# DC-DC_Converter.net
KiCad netlist of a schematic drawn in Altium Designer
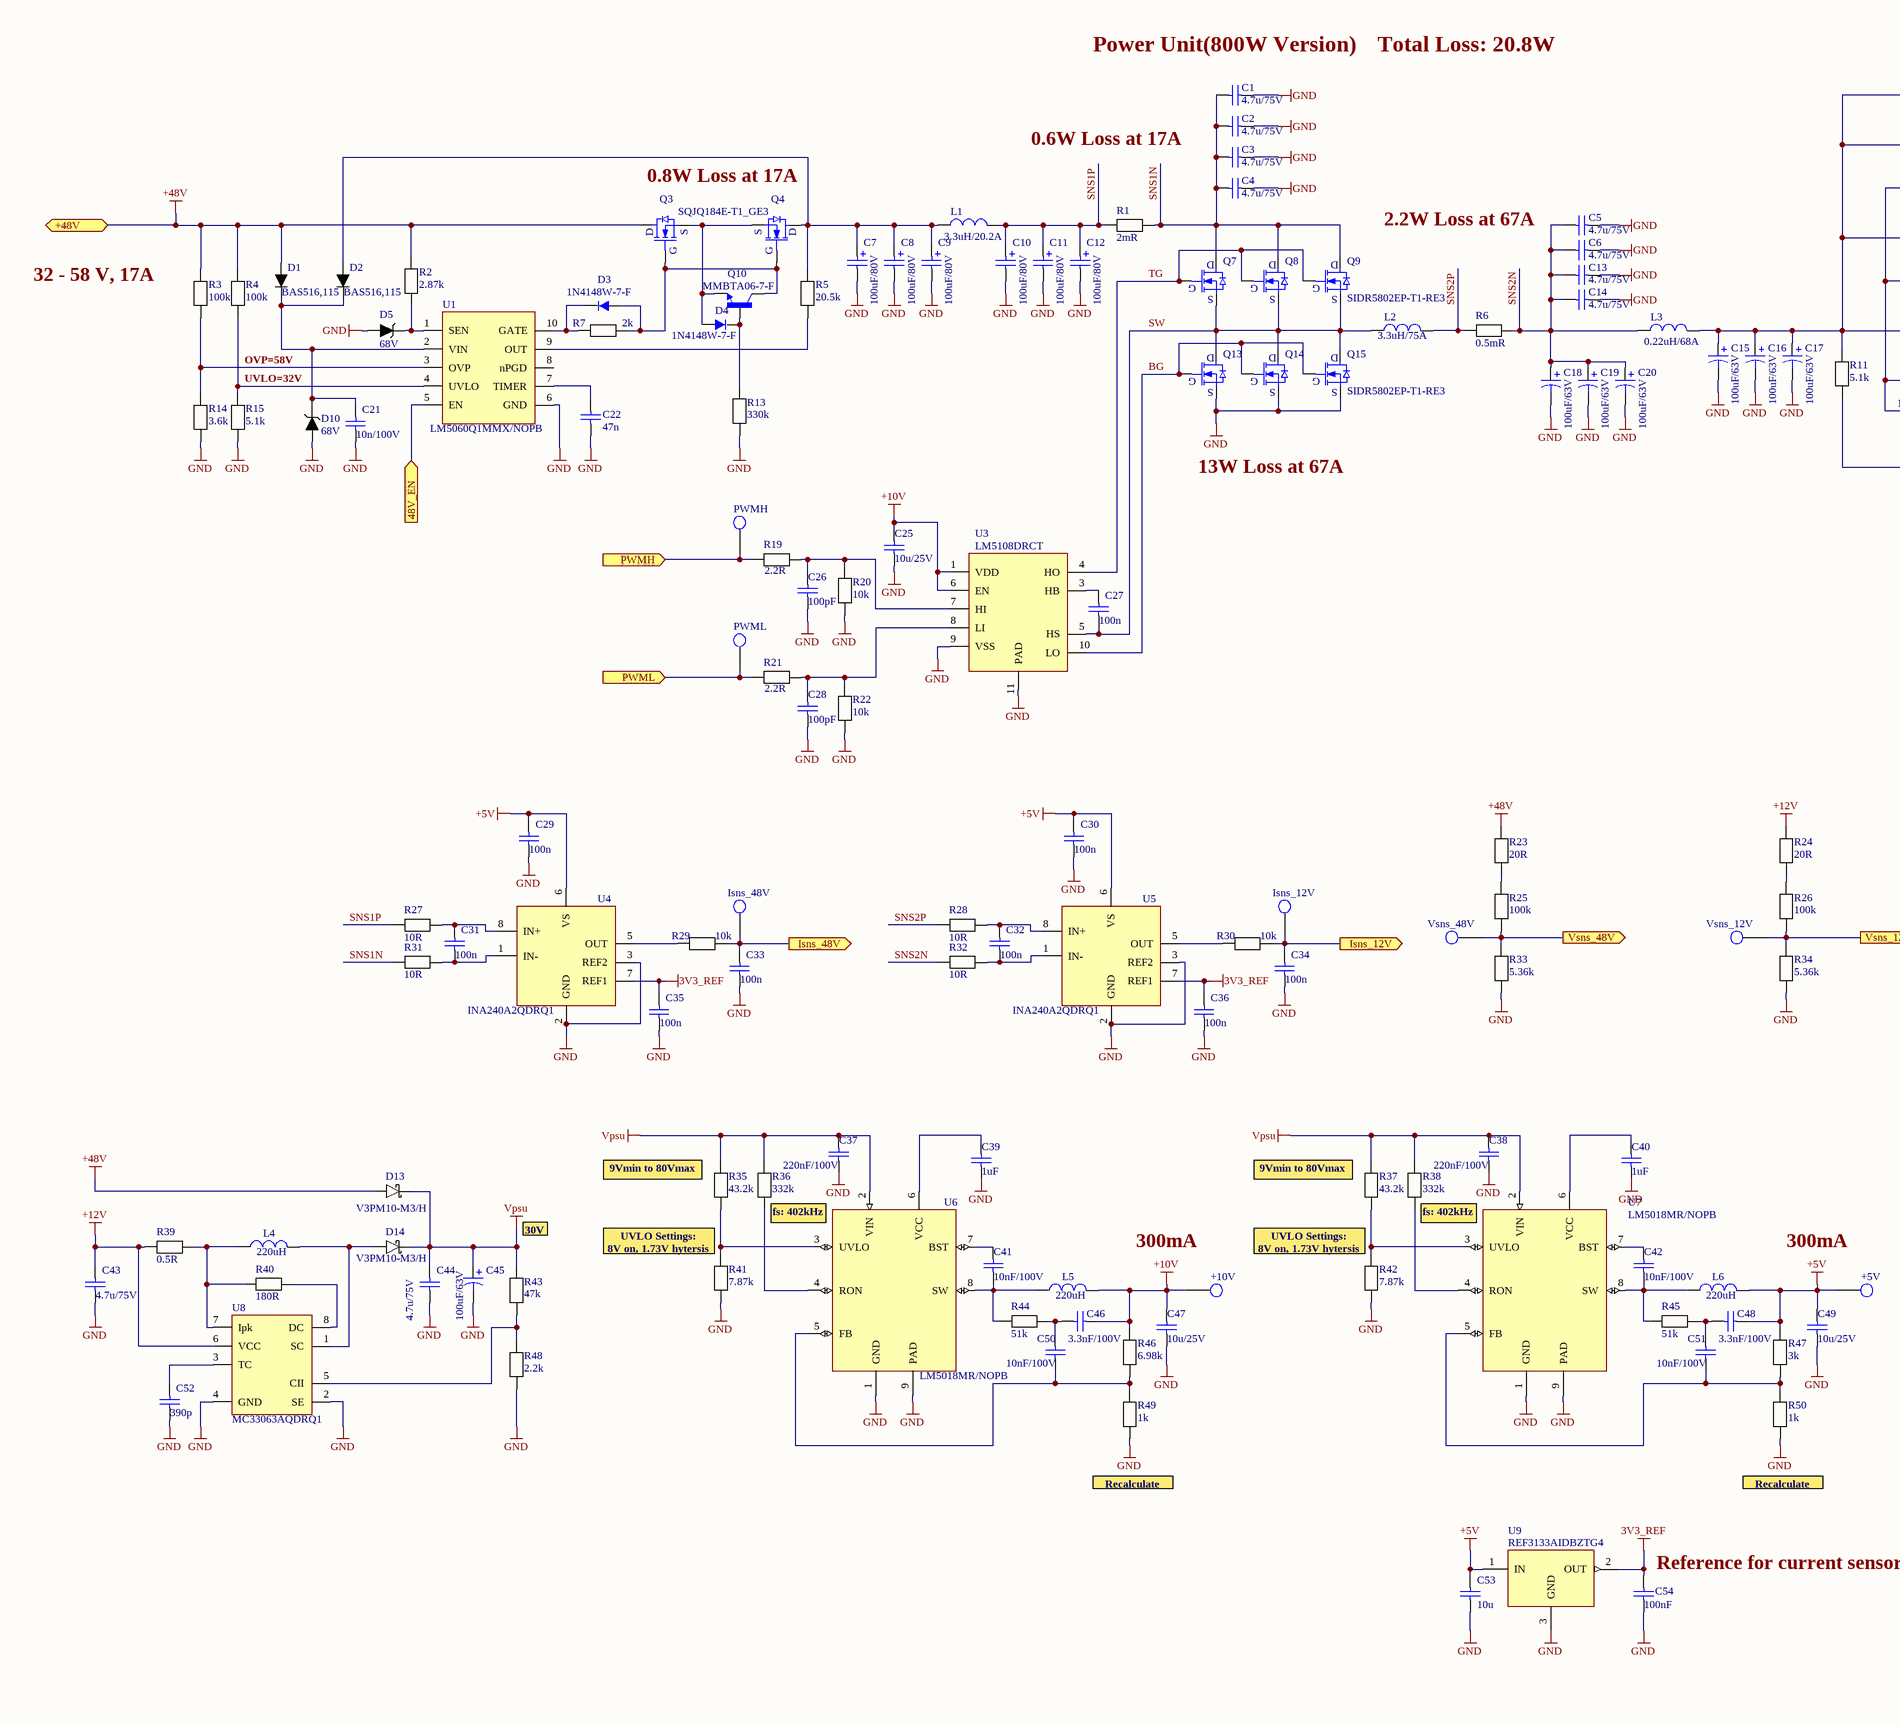
[diagram p0: DC-DC_Converter.SchDoc, left]
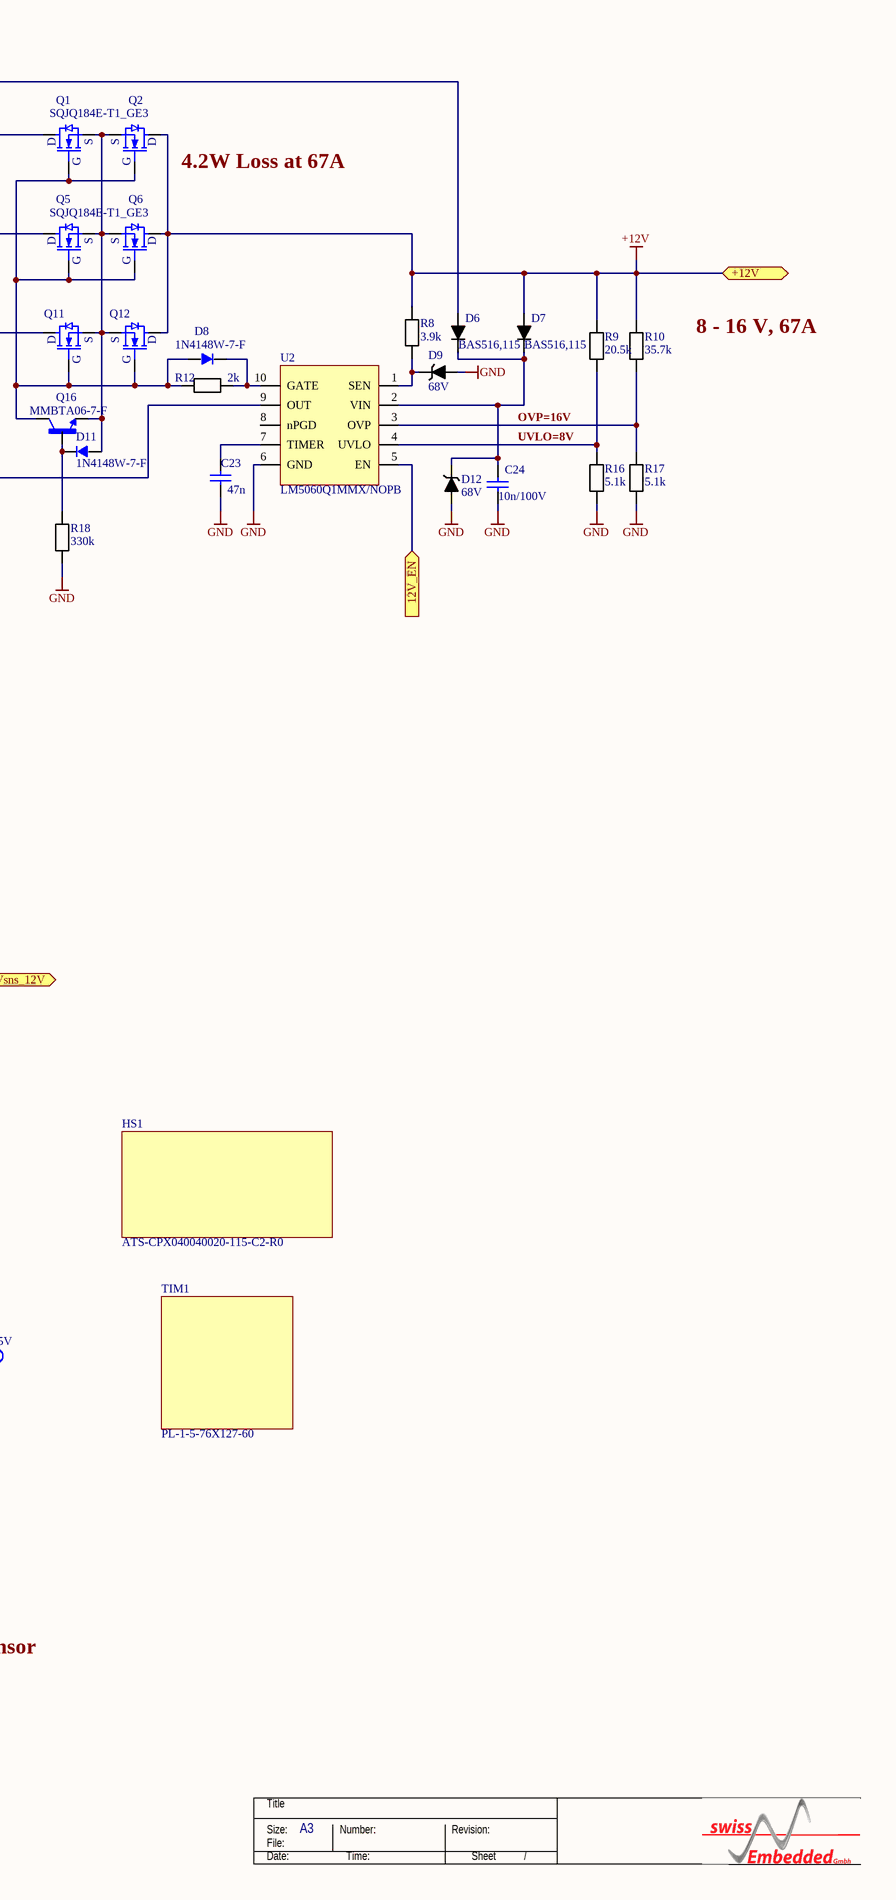
[diagram p1: DC-DC_Converter.SchDoc, right]

(export (version "E")
  (design (tool "Eeschema 10.0.6"))
  (components
    (comp (ref "+5V")
      (value "NO FIT")
      (footprint "TP_1")
      (description "Testpoint")
      (fields
        (field (name "MANUFACTURER") "None")
        (field (name "MANUFACTURER PART NUMBER") "Testpads, do not populate")
      )
      (libsource (lib "EnergyMeter") (part "TP"))
    )
    (comp (ref "+10V")
      (value "NO FIT")
      (footprint "TP_1")
      (description "Testpoint")
      (fields
        (field (name "MANUFACTURER") "None")
        (field (name "MANUFACTURER PART NUMBER") "Testpads, do not populate")
      )
      (libsource (lib "EnergyMeter") (part "TP"))
    )
    (comp (ref "C1")
      (value "4.7u/75V")
      (footprint "C1210")
      (description "4.7uF ±10% 75V")
      (fields
        (field (name "MANUFACTURER") "TDK")
        (field (name "MANUFACTURER PART NUMBER") "C3225X7R1N106K250AC")
      )
      (libsource (lib "EMDO601_Patch") (part "C3225X7R1N106K250AC"))
    )
    (comp (ref "C2")
      (value "4.7u/75V")
      (footprint "C1210")
      (description "4.7uF ±10% 75V")
      (fields
        (field (name "MANUFACTURER") "TDK")
        (field (name "MANUFACTURER PART NUMBER") "C3225X7R1N106K250AC")
      )
      (libsource (lib "EMDO601_Patch") (part "C3225X7R1N106K250AC"))
    )
    (comp (ref "C3")
      (value "4.7u/75V")
      (footprint "C1210")
      (description "4.7uF ±10% 75V")
      (fields
        (field (name "MANUFACTURER") "TDK")
        (field (name "MANUFACTURER PART NUMBER") "C3225X7R1N106K250AC")
      )
      (libsource (lib "EMDO601_Patch") (part "C3225X7R1N106K250AC"))
    )
    (comp (ref "C4")
      (value "4.7u/75V")
      (footprint "C1210")
      (description "4.7uF ±10% 75V")
      (fields
        (field (name "MANUFACTURER") "TDK")
        (field (name "MANUFACTURER PART NUMBER") "C3225X7R1N106K250AC")
      )
      (libsource (lib "EMDO601_Patch") (part "C3225X7R1N106K250AC"))
    )
    (comp (ref "C5")
      (value "4.7u/75V")
      (footprint "C1210")
      (description "4.7uF ±10% 75V")
      (fields
        (field (name "MANUFACTURER") "TDK")
        (field (name "MANUFACTURER PART NUMBER") "C3225X7R1N106K250AC")
      )
      (libsource (lib "EMDO601_Patch") (part "C3225X7R1N106K250AC"))
    )
    (comp (ref "C6")
      (value "4.7u/75V")
      (footprint "C1210")
      (description "4.7uF ±10% 75V")
      (fields
        (field (name "MANUFACTURER") "TDK")
        (field (name "MANUFACTURER PART NUMBER") "C3225X7R1N106K250AC")
      )
      (libsource (lib "EMDO601_Patch") (part "C3225X7R1N106K250AC"))
    )
    (comp (ref "C7")
      (value "100uF/80V")
      (footprint "CAP_80SXV47M")
      (description "100uF ±20% 80V")
      (fields
        (field (name "MANUFACTURER PART NUMBER") "MAL215099702E3")
        (field (name "MANUFACTURER") "Vishay / BC Components")
      )
      (libsource (lib "EMDO601_Patch") (part "100uF ±20% 80V"))
    )
    (comp (ref "C8")
      (value "100uF/80V")
      (footprint "CAP_80SXV47M")
      (description "100uF ±20% 80V")
      (fields
        (field (name "MANUFACTURER PART NUMBER") "MAL215099702E3")
        (field (name "MANUFACTURER") "Vishay / BC Components")
      )
      (libsource (lib "EMDO601_Patch") (part "100uF ±20% 80V"))
    )
    (comp (ref "C9")
      (value "100uF/80V")
      (footprint "CAP_80SXV47M")
      (description "100uF ±20% 80V")
      (fields
        (field (name "MANUFACTURER PART NUMBER") "MAL215099702E3")
        (field (name "MANUFACTURER") "Vishay / BC Components")
      )
      (libsource (lib "EMDO601_Patch") (part "100uF ±20% 80V"))
    )
    (comp (ref "C10")
      (value "100uF/80V")
      (footprint "CAP_80SXV47M")
      (description "100uF ±20% 80V")
      (fields
        (field (name "MANUFACTURER PART NUMBER") "MAL215099702E3")
        (field (name "MANUFACTURER") "Vishay / BC Components")
      )
      (libsource (lib "EMDO601_Patch") (part "100uF ±20% 80V"))
    )
    (comp (ref "C11")
      (value "100uF/80V")
      (footprint "CAP_80SXV47M")
      (description "100uF ±20% 80V")
      (fields
        (field (name "MANUFACTURER PART NUMBER") "MAL215099702E3")
        (field (name "MANUFACTURER") "Vishay / BC Components")
      )
      (libsource (lib "EMDO601_Patch") (part "100uF ±20% 80V"))
    )
    (comp (ref "C12")
      (value "100uF/80V")
      (footprint "CAP_80SXV47M")
      (description "100uF ±20% 80V")
      (fields
        (field (name "MANUFACTURER PART NUMBER") "MAL215099702E3")
        (field (name "MANUFACTURER") "Vishay / BC Components")
      )
      (libsource (lib "EMDO601_Patch") (part "100uF ±20% 80V"))
    )
    (comp (ref "C13")
      (value "4.7u/75V")
      (footprint "C1210")
      (description "4.7uF ±10% 75V")
      (fields
        (field (name "MANUFACTURER") "TDK")
        (field (name "MANUFACTURER PART NUMBER") "C3225X7R1N106K250AC")
      )
      (libsource (lib "EMDO601_Patch") (part "C3225X7R1N106K250AC"))
    )
    (comp (ref "C14")
      (value "4.7u/75V")
      (footprint "C1210")
      (description "4.7uF ±10% 75V")
      (fields
        (field (name "MANUFACTURER") "TDK")
        (field (name "MANUFACTURER PART NUMBER") "C3225X7R1N106K250AC")
      )
      (libsource (lib "EMDO601_Patch") (part "C3225X7R1N106K250AC"))
    )
    (comp (ref "C15")
      (value "100uF/63V")
      (footprint "CAP_80SXV47M")
      (description "100uF ±20% 63V")
      (fields
        (field (name "MANUFACTURER PART NUMBER") "A771MS107M1JLAS018")
        (field (name "MANUFACTURER") "KEMET")
      )
      (libsource (lib "Miscellaneous Devices") (part "Cap Pol1"))
    )
    (comp (ref "C16")
      (value "100uF/63V")
      (footprint "CAP_80SXV47M")
      (description "100uF ±20% 63V")
      (fields
        (field (name "MANUFACTURER PART NUMBER") "A771MS107M1JLAS018")
        (field (name "MANUFACTURER") "KEMET")
      )
      (libsource (lib "Miscellaneous Devices") (part "Cap Pol1"))
    )
    (comp (ref "C17")
      (value "100uF/63V")
      (footprint "CAP_80SXV47M")
      (description "100uF ±20% 63V")
      (fields
        (field (name "MANUFACTURER PART NUMBER") "A771MS107M1JLAS018")
        (field (name "MANUFACTURER") "KEMET")
      )
      (libsource (lib "Miscellaneous Devices") (part "Cap Pol1"))
    )
    (comp (ref "C18")
      (value "100uF/63V")
      (footprint "CAP_80SXV47M")
      (description "100uF ±20% 63V")
      (fields
        (field (name "MANUFACTURER PART NUMBER") "A771MS107M1JLAS018")
        (field (name "MANUFACTURER") "KEMET")
      )
      (libsource (lib "Miscellaneous Devices") (part "Cap Pol1"))
    )
    (comp (ref "C19")
      (value "100uF/63V")
      (footprint "CAP_80SXV47M")
      (description "100uF ±20% 63V")
      (fields
        (field (name "MANUFACTURER PART NUMBER") "A771MS107M1JLAS018")
        (field (name "MANUFACTURER") "KEMET")
      )
      (libsource (lib "Miscellaneous Devices") (part "Cap Pol1"))
    )
    (comp (ref "C20")
      (value "100uF/63V")
      (footprint "CAP_80SXV47M")
      (description "100uF ±20% 63V")
      (fields
        (field (name "MANUFACTURER PART NUMBER") "A771MS107M1JLAS018")
        (field (name "MANUFACTURER") "KEMET")
      )
      (libsource (lib "Miscellaneous Devices") (part "Cap Pol1"))
    )
    (comp (ref "C21")
      (value "10n/100V")
      (footprint "C0805")
      (description "10nF ±10% 100V")
      (fields
        (field (name "MANUFACTURER") "Yageo")
        (field (name "MANUFACTURER PART NUMBER") "CC0805KPX7R0BB103")
      )
      (libsource (lib "EMDO601_Patch") (part "10nF ±10% 100V"))
    )
    (comp (ref "C22")
      (value "47n")
      (footprint "C0603")
      (description "47nF ±10% 50V")
      (fields
        (field (name "MANUFACTURER") "Yageo")
        (field (name "MANUFACTURER PART NUMBER") "CC0603KRX7R9BB473")
      )
      (libsource (lib "EMDO601_Patch") (part "47nF ±10% 50V"))
    )
    (comp (ref "C23")
      (value "47n")
      (footprint "C0603")
      (description "47nF ±10% 50V")
      (fields
        (field (name "MANUFACTURER") "Yageo")
        (field (name "MANUFACTURER PART NUMBER") "CC0603KRX7R9BB473")
      )
      (libsource (lib "EMDO601_Patch") (part "47nF ±10% 50V"))
    )
    (comp (ref "C24")
      (value "10n/100V")
      (footprint "C0805")
      (description "10nF ±10% 100V")
      (fields
        (field (name "MANUFACTURER") "Yageo")
        (field (name "MANUFACTURER PART NUMBER") "CC0805KPX7R0BB103")
      )
      (libsource (lib "EMDO601_Patch") (part "10nF ±10% 100V"))
    )
    (comp (ref "C25")
      (value "10u/25V")
      (footprint "C0805")
      (description "10uF ±10% 25V")
      (fields
        (field (name "MANUFACTURER") "Yageo")
        (field (name "MANUFACTURER PART NUMBER") "CC0805KKX5R8BB106")
      )
      (libsource (lib "RCL") (part "CAP"))
    )
    (comp (ref "C26")
      (value "100pF")
      (footprint "C0603")
      (description "100pF ±10% 50V")
      (fields
        (field (name "MANUFACTURER") "Yageo")
        (field (name "MANUFACTURER PART NUMBER") "CC0603KRNPO9BN101")
      )
      (libsource (lib "RCL") (part "CAP"))
    )
    (comp (ref "C27")
      (value "100n")
      (footprint "C0603")
      (description "100nF ±10% 50V")
      (fields
        (field (name "PART NUMBER") "CAP_YAG_CC0603KRX7R9BB104_X7R")
        (field (name "MANUFACTURER") "Yageo")
      )
      (libsource (lib "Cap_Yag_0603_X7R_50_10%$") (part "CAP_YAG_CC0603KRX7R9BB104_X7R"))
    )
    (comp (ref "C28")
      (value "100pF")
      (footprint "C0603")
      (description "100pF ±10% 50V")
      (fields
        (field (name "MANUFACTURER") "Yageo")
        (field (name "MANUFACTURER PART NUMBER") "CC0603KRNPO9BN101")
      )
      (libsource (lib "RCL") (part "CAP"))
    )
    (comp (ref "C29")
      (value "100n")
      (footprint "C0603")
      (description "100nF ±10% 50V")
      (fields
        (field (name "PART NUMBER") "CAP_YAG_CC0603KRX7R9BB104_X7R")
        (field (name "MANUFACTURER") "Yageo")
      )
      (libsource (lib "Cap_Yag_0603_X7R_50_10%$") (part "CAP_YAG_CC0603KRX7R9BB104_X7R"))
    )
    (comp (ref "C30")
      (value "100n")
      (footprint "C0603")
      (description "100nF ±10% 50V")
      (fields
        (field (name "PART NUMBER") "CAP_YAG_CC0603KRX7R9BB104_X7R")
        (field (name "MANUFACTURER") "Yageo")
      )
      (libsource (lib "Cap_Yag_0603_X7R_50_10%$") (part "CAP_YAG_CC0603KRX7R9BB104_X7R"))
    )
    (comp (ref "C31")
      (value "100n")
      (footprint "C0603")
      (description "100nF ±10% 50V")
      (fields
        (field (name "PART NUMBER") "CAP_YAG_CC0603KRX7R9BB104_X7R")
        (field (name "MANUFACTURER") "Yageo")
      )
      (libsource (lib "Cap_Yag_0603_X7R_50_10%$") (part "CAP_YAG_CC0603KRX7R9BB104_X7R"))
    )
    (comp (ref "C32")
      (value "100n")
      (footprint "C0603")
      (description "100nF ±10% 50V")
      (fields
        (field (name "PART NUMBER") "CAP_YAG_CC0603KRX7R9BB104_X7R")
        (field (name "MANUFACTURER") "Yageo")
      )
      (libsource (lib "Cap_Yag_0603_X7R_50_10%$") (part "CAP_YAG_CC0603KRX7R9BB104_X7R"))
    )
    (comp (ref "C33")
      (value "100n")
      (footprint "C0603")
      (description "100nF ±10% 50V")
      (fields
        (field (name "PART NUMBER") "CAP_YAG_CC0603KRX7R9BB104_X7R")
        (field (name "MANUFACTURER") "Yageo")
      )
      (libsource (lib "Cap_Yag_0603_X7R_50_10%$") (part "CAP_YAG_CC0603KRX7R9BB104_X7R"))
    )
    (comp (ref "C34")
      (value "100n")
      (footprint "C0603")
      (description "100nF ±10% 50V")
      (fields
        (field (name "PART NUMBER") "CAP_YAG_CC0603KRX7R9BB104_X7R")
        (field (name "MANUFACTURER") "Yageo")
      )
      (libsource (lib "Cap_Yag_0603_X7R_50_10%$") (part "CAP_YAG_CC0603KRX7R9BB104_X7R"))
    )
    (comp (ref "C35")
      (value "100n")
      (footprint "C0603")
      (description "100nF ±10% 50V")
      (fields
        (field (name "PART NUMBER") "CAP_YAG_CC0603KRX7R9BB104_X7R")
        (field (name "MANUFACTURER") "Yageo")
      )
      (libsource (lib "Cap_Yag_0603_X7R_50_10%$") (part "CAP_YAG_CC0603KRX7R9BB104_X7R"))
    )
    (comp (ref "C36")
      (value "100n")
      (footprint "C0603")
      (description "100nF ±10% 50V")
      (fields
        (field (name "PART NUMBER") "CAP_YAG_CC0603KRX7R9BB104_X7R")
        (field (name "MANUFACTURER") "Yageo")
      )
      (libsource (lib "Cap_Yag_0603_X7R_50_10%$") (part "CAP_YAG_CC0603KRX7R9BB104_X7R"))
    )
    (comp (ref "C37")
      (value "220nF/100V")
      (footprint "C0805")
      (description "220nF ±10% 100V")
      (fields
        (field (name "MANUFACTURER") "Yageo")
        (field (name "MANUFACTURER PART NUMBER") "CC0805KKX7R0BB224")
      )
      (libsource (lib "RCL") (part "CAP"))
    )
    (comp (ref "C38")
      (value "220nF/100V")
      (footprint "C0805")
      (description "220nF ±10% 100V")
      (fields
        (field (name "MANUFACTURER") "Yageo")
        (field (name "MANUFACTURER PART NUMBER") "CC0805KKX7R0BB224")
      )
      (libsource (lib "RCL") (part "CAP"))
    )
    (comp (ref "C39")
      (value "1uF")
      (footprint "C0603")
      (description "1uF ±10% 50V")
      (fields
        (field (name "MANUFACTURER") "Yageo")
        (field (name "MANUFACTURER PART NUMBER") "CC0603KRX7R9BB105")
      )
      (libsource (lib "RCL") (part "CAP"))
    )
    (comp (ref "C40")
      (value "1uF")
      (footprint "C0603")
      (description "1uF ±10% 50V")
      (fields
        (field (name "MANUFACTURER") "Yageo")
        (field (name "MANUFACTURER PART NUMBER") "CC0603KRX7R9BB105")
      )
      (libsource (lib "RCL") (part "CAP"))
    )
    (comp (ref "C41")
      (value "10nF/100V")
      (footprint "C0603")
      (description "10nF ±10% 100V")
      (fields
        (field (name "MANUFACTURER") "Yageo")
        (field (name "MANUFACTURER PART NUMBER") "CC0603KRX7R0BB103")
      )
      (libsource (lib "RCL") (part "CAP"))
    )
    (comp (ref "C42")
      (value "10nF/100V")
      (footprint "C0603")
      (description "10nF ±10% 100V")
      (fields
        (field (name "MANUFACTURER") "Yageo")
        (field (name "MANUFACTURER PART NUMBER") "CC0603KRX7R0BB103")
      )
      (libsource (lib "RCL") (part "CAP"))
    )
    (comp (ref "C43")
      (value "4.7u/75V")
      (footprint "C1210")
      (description "4.7uF ±10% 75V")
      (fields
        (field (name "MANUFACTURER") "TDK")
        (field (name "MANUFACTURER PART NUMBER") "C3225X7R1N106K250AC")
      )
      (libsource (lib "EMDO601_Patch") (part "C3225X7R1N106K250AC"))
    )
    (comp (ref "C44")
      (value "4.7u/75V")
      (footprint "C1210")
      (description "4.7uF ±10% 75V")
      (fields
        (field (name "MANUFACTURER") "TDK")
        (field (name "MANUFACTURER PART NUMBER") "C3225X7R1N106K250AC")
      )
      (libsource (lib "EMDO601_Patch") (part "C3225X7R1N106K250AC"))
    )
    (comp (ref "C45")
      (value "100uF/63V")
      (footprint "CAP_80SXV47M")
      (description "100uF ±20% 63V")
      (fields
        (field (name "MANUFACTURER PART NUMBER") "A771MS107M1JLAS018")
        (field (name "MANUFACTURER") "KEMET")
      )
      (libsource (lib "Miscellaneous Devices") (part "Cap Pol1"))
    )
    (comp (ref "C46")
      (value "3.3nF/100V")
      (footprint "C0603")
      (description "3.3nF ±10% 100V")
      (fields
        (field (name "MANUFACTURER") "Yageo")
        (field (name "MANUFACTURER PART NUMBER") "CC0603KRX7R0BB332")
      )
      (libsource (lib "RCL") (part "CAP"))
    )
    (comp (ref "C47")
      (value "10u/25V")
      (footprint "C0805")
      (description "10uF ±10% 25V")
      (fields
        (field (name "MANUFACTURER") "Yageo")
        (field (name "MANUFACTURER PART NUMBER") "CC0805KKX5R8BB106")
      )
      (libsource (lib "RCL") (part "CAP"))
    )
    (comp (ref "C48")
      (value "3.3nF/100V")
      (footprint "C0603")
      (description "3.3nF ±10% 100V")
      (fields
        (field (name "MANUFACTURER") "Yageo")
        (field (name "MANUFACTURER PART NUMBER") "CC0603KRX7R0BB332")
      )
      (libsource (lib "RCL") (part "CAP"))
    )
    (comp (ref "C49")
      (value "10u/25V")
      (footprint "C0805")
      (description "10uF ±10% 25V")
      (fields
        (field (name "MANUFACTURER") "Yageo")
        (field (name "MANUFACTURER PART NUMBER") "CC0805KKX5R8BB106")
      )
      (libsource (lib "RCL") (part "CAP"))
    )
    (comp (ref "C50")
      (value "10nF/100V")
      (footprint "C0603")
      (description "10nF ±10% 100V")
      (fields
        (field (name "MANUFACTURER") "Yageo")
        (field (name "MANUFACTURER PART NUMBER") "CC0603KRX7R0BB103")
      )
      (libsource (lib "RCL") (part "CAP"))
    )
    (comp (ref "C51")
      (value "10nF/100V")
      (footprint "C0603")
      (description "10nF ±10% 100V")
      (fields
        (field (name "MANUFACTURER") "Yageo")
        (field (name "MANUFACTURER PART NUMBER") "CC0603KRX7R0BB103")
      )
      (libsource (lib "RCL") (part "CAP"))
    )
    (comp (ref "C52")
      (value "390p")
      (footprint "C0603")
      (description "390pF ±10% 50V")
      (fields
        (field (name "MANUFACTURER") "Yageo")
        (field (name "MANUFACTURER PART NUMBER") "C0603JRNPO9BN391")
      )
      (libsource (lib "EMDO601_Patch") (part "390pF ±10% 50V"))
    )
    (comp (ref "C53")
      (value "10u")
      (footprint "C1206")
      (description "10uF ± 10% 25V")
      (fields
        (field (name "MANUFACTURER") "Yageo")
        (field (name "MANUFACTURER PART NUMBER") "CC1206KKX7R8BB106")
      )
      (libsource (lib "Humidity Regulator") (part "10uF ± 10% 25V"))
    )
    (comp (ref "C54")
      (value "100nF")
      (footprint "C0603")
      (description "100nF ± 10% 50V")
      (fields
        (field (name "MANUFACTURER") "Yageo")
        (field (name "MANUFACTURER PART NUMBER") "CC0603KRX7R9BB104")
      )
      (libsource (lib "Humidity Regulator") (part "100nF ± 10% 50V"))
    )
    (comp (ref "D1")
      (value "BAS516,115")
      (footprint "SOD523")
      (description "Diodes - General Purpose, Power, Switching BAS516/SOD523/SC-79")
      (fields (field (name "MANUFACTURER") "Nexperia"))
      (libsource (lib "EMDO601_Patch") (part "BAS516,115"))
    )
    (comp (ref "D2")
      (value "BAS516,115")
      (footprint "SOD523")
      (description "Diodes - General Purpose, Power, Switching BAS516/SOD523/SC-79")
      (fields (field (name "MANUFACTURER") "Nexperia"))
      (libsource (lib "EMDO601_Patch") (part "BAS516,115"))
    )
    (comp (ref "D3")
      (value "1N4148W-7-F")
      (footprint "SOD-123")
      (description "Diode Standard 100 V 300mA (DC) Surface Mount SOD-123")
      (fields (field (name "MANUFACTURER") "Diodes"))
      (libsource (lib "26-525 - CueLight Splitter") (part "1N4148W-7-F"))
    )
    (comp (ref "D4")
      (value "1N4148W-7-F")
      (footprint "SOD-123")
      (description "Diode Standard 100 V 300mA (DC) Surface Mount SOD-123")
      (fields (field (name "MANUFACTURER") "Diodes"))
      (libsource (lib "26-525 - CueLight Splitter") (part "1N4148W-7-F"))
    )
    (comp (ref "D5")
      (value "68V")
      (footprint "SOT23-3")
      (description "Zener Diodes BZX8450-C68/SOT23/TO-236AB")
      (fields
        (field (name "MANUFACTURER") "Nexperia")
        (field (name "MANUFACTURER PART NUMBER") "BZX8450-C68R")
      )
      (libsource (lib "EMDO601_Patch") (part "BZX8450-C68R"))
    )
    (comp (ref "D6")
      (value "BAS516,115")
      (footprint "SOD523")
      (description "Diodes - General Purpose, Power, Switching BAS516/SOD523/SC-79")
      (fields (field (name "MANUFACTURER") "Nexperia"))
      (libsource (lib "EMDO601_Patch") (part "BAS516,115"))
    )
    (comp (ref "D7")
      (value "BAS516,115")
      (footprint "SOD523")
      (description "Diodes - General Purpose, Power, Switching BAS516/SOD523/SC-79")
      (fields (field (name "MANUFACTURER") "Nexperia"))
      (libsource (lib "EMDO601_Patch") (part "BAS516,115"))
    )
    (comp (ref "D8")
      (value "1N4148W-7-F")
      (footprint "SOD-123")
      (description "Diode Standard 100 V 300mA (DC) Surface Mount SOD-123")
      (fields (field (name "MANUFACTURER") "Diodes"))
      (libsource (lib "26-525 - CueLight Splitter") (part "1N4148W-7-F"))
    )
    (comp (ref "D9")
      (value "68V")
      (footprint "SOT23-3")
      (description "Zener Diodes BZX8450-C68/SOT23/TO-236AB")
      (fields
        (field (name "MANUFACTURER") "Nexperia")
        (field (name "MANUFACTURER PART NUMBER") "BZX8450-C68R")
      )
      (libsource (lib "EMDO601_Patch") (part "BZX8450-C68R"))
    )
    (comp (ref "D10")
      (value "68V")
      (footprint "SOT23-3")
      (description "Zener Diodes BZX8450-C68/SOT23/TO-236AB")
      (fields
        (field (name "MANUFACTURER") "Nexperia")
        (field (name "MANUFACTURER PART NUMBER") "BZX8450-C68R")
      )
      (libsource (lib "EMDO601_Patch") (part "BZX8450-C68R"))
    )
    (comp (ref "D11")
      (value "1N4148W-7-F")
      (footprint "SOD-123")
      (description "Diode Standard 100 V 300mA (DC) Surface Mount SOD-123")
      (fields (field (name "MANUFACTURER") "Diodes"))
      (libsource (lib "26-525 - CueLight Splitter") (part "1N4148W-7-F"))
    )
    (comp (ref "D12")
      (value "68V")
      (footprint "SOT23-3")
      (description "Zener Diodes BZX8450-C68/SOT23/TO-236AB")
      (fields
        (field (name "MANUFACTURER") "Nexperia")
        (field (name "MANUFACTURER PART NUMBER") "BZX8450-C68R")
      )
      (libsource (lib "EMDO601_Patch") (part "BZX8450-C68R"))
    )
    (comp (ref "D13")
      (value "V3PM10-M3/H")
      (footprint "DO-220AA")
      (description "Schottky Diodes & Rectifiers 100V 3A TMBS SMP")
      (fields (field (name "MANUFACTURER") "Vishay"))
      (libsource (lib "EMDO601_Patch") (part "V3PM10-M3/H"))
    )
    (comp (ref "D14")
      (value "V3PM10-M3/H")
      (footprint "DO-220AA")
      (description "Schottky Diodes & Rectifiers 100V 3A TMBS SMP")
      (fields (field (name "MANUFACTURER") "Vishay"))
      (libsource (lib "EMDO601_Patch") (part "V3PM10-M3/H"))
    )
    (comp (ref "HS1")
      (value "ATS-CPX040040020-115-C2-R0")
      (footprint "HeatSink_ATS-CPX040040020-115-C2-R0")
      (description "Heat Sinks pushPIN Heat Sink, Blue-Anodized, 40x40x20mm")
      (fields (field (name "MANUFACTURER") "Advanced Thermal Solutions"))
      (libsource (lib "EMDO601_Patch") (part "ATS-CPX040040020-115-C2-R0"))
    )
    (comp (ref "Isns_12V")
      (value "NO FIT")
      (footprint "TP_1")
      (description "Testpoint")
      (fields
        (field (name "MANUFACTURER") "None")
        (field (name "MANUFACTURER PART NUMBER") "Testpads, do not populate")
      )
      (libsource (lib "EnergyMeter") (part "TP"))
    )
    (comp (ref "Isns_48V")
      (value "NO FIT")
      (footprint "TP_1")
      (description "Testpoint")
      (fields
        (field (name "MANUFACTURER") "None")
        (field (name "MANUFACTURER PART NUMBER") "Testpads, do not populate")
      )
      (libsource (lib "EnergyMeter") (part "TP"))
    )
    (comp (ref "L1")
      (value "3.3uH/20.2A")
      (footprint "IND_IHLP5050FDER3R3M5A")
      (description "Power Inductors - SMD 3.3uH 20% High Temp AEC-Q200")
      (fields
        (field (name "MANUFACTURER PART NUMBER") "IHLP5050FDER3R3M5A")
        (field (name "MANUFACTURER") "Vishay")
      )
      (libsource (lib "EMDO601_Patch") (part "IHLP5050FDER3R3M5A"))
    )
    (comp (ref "L2")
      (value "3.3uH/75A")
      (footprint "IND_7443763521033")
      (description "Power Inductors - Leaded WE-HCFT 3521 3.3uH 20% 75A 0.4mOh")
      (fields
        (field (name "MANUFACTURER PART NUMBER") "7443763521033")
        (field (name "MANUFACTURER") "Wurth Elektronik")
      )
      (libsource (lib "EMDO601_Patch") (part "7443763521033"))
    )
    (comp (ref "L3")
      (value "0.22uH/68A")
      (footprint "IND_IHLP5050EZERR22M5A")
      (description "Power Inductors - SMD 0.22uH 20% High Temp AEC-Q200")
      (fields
        (field (name "MANUFACTURER PART NUMBER") "IHLP5050EZERR22M5A")
        (field (name "MANUFACTURER") "Vishay")
      )
      (libsource (lib "EMDO601_Patch") (part "IHLP5050EZERR22M5A"))
    )
    (comp (ref "L4")
      (value "220uH")
      (footprint "IND_SRN6045")
      (description "Power Inductors - SMD 220uH 20% SMD 6045")
      (fields (field (name "MANUFACTURER PART NUMBER") "SRN6045-221M") (field (name "MANUFACTURER") "Bourns"))
      (libsource (lib "WirelessCharger") (part "Inductor"))
    )
    (comp (ref "L5")
      (value "220uH")
      (footprint "IND_SRN6045")
      (description "Power Inductors - SMD 220uH 20% SMD 6045")
      (fields (field (name "MANUFACTURER PART NUMBER") "SRN6045-221M") (field (name "MANUFACTURER") "Bourns"))
      (libsource (lib "WirelessCharger") (part "Inductor"))
    )
    (comp (ref "L6")
      (value "220uH")
      (footprint "IND_SRN6045")
      (description "Power Inductors - SMD 220uH 20% SMD 6045")
      (fields (field (name "MANUFACTURER PART NUMBER") "SRN6045-221M") (field (name "MANUFACTURER") "Bourns"))
      (libsource (lib "WirelessCharger") (part "Inductor"))
    )
    (comp (ref "PWMH")
      (value "NO FIT")
      (footprint "TP_1")
      (description "Testpoint")
      (fields
        (field (name "MANUFACTURER") "None")
        (field (name "MANUFACTURER PART NUMBER") "Testpads, do not populate")
      )
      (libsource (lib "EnergyMeter") (part "TP"))
    )
    (comp (ref "PWML")
      (value "NO FIT")
      (footprint "TP_1")
      (description "Testpoint")
      (fields
        (field (name "MANUFACTURER") "None")
        (field (name "MANUFACTURER PART NUMBER") "Testpads, do not populate")
      )
      (libsource (lib "EnergyMeter") (part "TP"))
    )
    (comp (ref "Q1")
      (value "SQJQ184E-T1_GE3")
      (footprint "PowerPAK8x8L")
      (description "MOSFET N-Ch 80V 430A")
      (fields (field (name "MANUFACTURER") "Vishay Semiconductors"))
      (libsource (lib "EMDO601_Patch") (part "SQJQ184E-T1_GE3"))
    )
    (comp (ref "Q2")
      (value "SQJQ184E-T1_GE3")
      (footprint "PowerPAK8x8L")
      (description "MOSFET N-Ch 80V 430A")
      (fields (field (name "MANUFACTURER") "Vishay Semiconductors"))
      (libsource (lib "EMDO601_Patch") (part "SQJQ184E-T1_GE3"))
    )
    (comp (ref "Q3")
      (value "SQJQ184E-T1_GE3")
      (footprint "PowerPAK8x8L")
      (description "MOSFET N-Ch 80V 430A")
      (fields (field (name "MANUFACTURER") "Vishay Semiconductors"))
      (libsource (lib "EMDO601_Patch") (part "SQJQ184E-T1_GE3"))
    )
    (comp (ref "Q4")
      (value "SQJQ184E-T1_GE3")
      (footprint "PowerPAK8x8L")
      (description "MOSFET N-Ch 80V 430A")
      (fields (field (name "MANUFACTURER") "Vishay Semiconductors"))
      (libsource (lib "EMDO601_Patch") (part "SQJQ184E-T1_GE3"))
    )
    (comp (ref "Q5")
      (value "SQJQ184E-T1_GE3")
      (footprint "PowerPAK8x8L")
      (description "MOSFET N-Ch 80V 430A")
      (fields (field (name "MANUFACTURER") "Vishay Semiconductors"))
      (libsource (lib "EMDO601_Patch") (part "SQJQ184E-T1_GE3"))
    )
    (comp (ref "Q6")
      (value "SQJQ184E-T1_GE3")
      (footprint "PowerPAK8x8L")
      (description "MOSFET N-Ch 80V 430A")
      (fields (field (name "MANUFACTURER") "Vishay Semiconductors"))
      (libsource (lib "EMDO601_Patch") (part "SQJQ184E-T1_GE3"))
    )
    (comp (ref "Q7")
      (value "SIDR5802EP-T1-RE3")
      (footprint "PowerPAK SO-8DC")
      (description "MOSFET N-Ch 80V 153A, 28nC")
      (fields (field (name "MANUFACTURER") "Vishay Semiconductors"))
      (libsource (lib "EMDO601_Patch") (part "SIDR5802EP-T1-RE3"))
    )
    (comp (ref "Q8")
      (value "SIDR5802EP-T1-RE3")
      (footprint "PowerPAK SO-8DC")
      (description "MOSFET N-Ch 80V 153A, 28nC")
      (fields (field (name "MANUFACTURER") "Vishay Semiconductors"))
      (libsource (lib "EMDO601_Patch") (part "SIDR5802EP-T1-RE3"))
    )
    (comp (ref "Q9")
      (value "SIDR5802EP-T1-RE3")
      (footprint "PowerPAK SO-8DC")
      (description "MOSFET N-Ch 80V 153A, 28nC")
      (fields (field (name "MANUFACTURER") "Vishay Semiconductors"))
      (libsource (lib "EMDO601_Patch") (part "SIDR5802EP-T1-RE3"))
    )
    (comp (ref "Q10")
      (value "MMBTA06-7-F")
      (footprint "SOT23-3")
      (description "Bipolar Transistors - BJT 80V 300mW")
      (fields (field (name "MANUFACTURER") "Diodes Incorporated"))
      (libsource (lib "EMDO601_Patch") (part "MMBTA06-7-F"))
    )
    (comp (ref "Q11")
      (value "SQJQ184E-T1_GE3")
      (footprint "PowerPAK8x8L")
      (description "MOSFET N-Ch 80V 430A")
      (fields (field (name "MANUFACTURER") "Vishay Semiconductors"))
      (libsource (lib "EMDO601_Patch") (part "SQJQ184E-T1_GE3"))
    )
    (comp (ref "Q12")
      (value "SQJQ184E-T1_GE3")
      (footprint "PowerPAK8x8L")
      (description "MOSFET N-Ch 80V 430A")
      (fields (field (name "MANUFACTURER") "Vishay Semiconductors"))
      (libsource (lib "EMDO601_Patch") (part "SQJQ184E-T1_GE3"))
    )
    (comp (ref "Q13")
      (value "SIDR5802EP-T1-RE3")
      (footprint "PowerPAK SO-8DC")
      (description "MOSFET N-Ch 80V 153A, 28nC")
      (fields (field (name "MANUFACTURER") "Vishay Semiconductors"))
      (libsource (lib "EMDO601_Patch") (part "SIDR5802EP-T1-RE3"))
    )
    (comp (ref "Q14")
      (value "SIDR5802EP-T1-RE3")
      (footprint "PowerPAK SO-8DC")
      (description "MOSFET N-Ch 80V 153A, 28nC")
      (fields (field (name "MANUFACTURER") "Vishay Semiconductors"))
      (libsource (lib "EMDO601_Patch") (part "SIDR5802EP-T1-RE3"))
    )
    (comp (ref "Q15")
      (value "SIDR5802EP-T1-RE3")
      (footprint "PowerPAK SO-8DC")
      (description "MOSFET N-Ch 80V 153A, 28nC")
      (fields (field (name "MANUFACTURER") "Vishay Semiconductors"))
      (libsource (lib "EMDO601_Patch") (part "SIDR5802EP-T1-RE3"))
    )
    (comp (ref "Q16")
      (value "MMBTA06-7-F")
      (footprint "SOT23-3")
      (description "Bipolar Transistors - BJT 80V 300mW")
      (fields (field (name "MANUFACTURER") "Diodes Incorporated"))
      (libsource (lib "") (part "MMBTA06-7-F_1"))
    )
    (comp (ref "R1")
      (value "2mR")
      (footprint "R3921")
      (description "5W/ 2mohm±1%")
      (fields
        (field (name "MANUFACTURER PART NUMBER") "WSLP39212L000FEA")
        (field (name "MANUFACTURER") "Vishay / Dale")
      )
      (libsource (lib "EMDO601_Patch") (part "WSLP39212L000FEA"))
    )
    (comp (ref "R2")
      (value "2.87k")
      (footprint "R0603")
      (description "2.87 kohm ±1% 0.1W")
      (fields (field (name "MANUFACTURER PART NUMBER") "RC0603FR-072K87L") (field (name "TOLERANCE") "+-1%"))
      (libsource (lib "EMDO601_Patch") (part "2.87 kohm ±1% 0.1W"))
    )
    (comp (ref "R3")
      (value "100k")
      (footprint "R0603")
      (description "100 kohm ±1% 0.1W")
      (fields (field (name "MANUFACTURER PART NUMBER") "RC0603FR-07100KL") (field (name "TOLERANCE") "+-1%"))
      (libsource (lib "EMDO601_Patch") (part "100 kohm ±1% 0.1W"))
    )
    (comp (ref "R4")
      (value "100k")
      (footprint "R0603")
      (description "100 kohm ±1% 0.1W")
      (fields (field (name "MANUFACTURER PART NUMBER") "RC0603FR-07100KL") (field (name "TOLERANCE") "+-1%"))
      (libsource (lib "EMDO601_Patch") (part "100 kohm ±1% 0.1W"))
    )
    (comp (ref "R5")
      (value "20.5k")
      (footprint "R0603")
      (description "20.5 kohm ±1% 0.1W")
      (fields (field (name "MANUFACTURER PART NUMBER") "RC0603FR-0720K5L") (field (name "TOLERANCE") "+-1%"))
      (libsource (lib "EMDO601_Patch") (part "20.5 kohm ±1% 0.1W"))
    )
    (comp (ref "R6")
      (value "0.5mR")
      (footprint "R3921")
      (description "9W/ 0.5mohm±1%")
      (fields
        (field (name "MANUFACTURER PART NUMBER") "WSLP3921L5000FEB")
        (field (name "MANUFACTURER") "Vishay / Dale")
      )
      (libsource (lib "EMDO601_Patch") (part "WSLP3921L5000FEB"))
    )
    (comp (ref "R7")
      (value "2k")
      (footprint "R0603")
      (description "2 kohm ±1% 0.1W")
      (fields (field (name "MANUFACTURER PART NUMBER") "RC0603FR-072KL") (field (name "TOLERANCE") "+-1%"))
      (libsource (lib "EMDO601_Patch") (part "2 kohm ±1% 0.1W"))
    )
    (comp (ref "R8")
      (value "3.9k")
      (footprint "R0603")
      (description "3.9 kohm ±1% 0.1W")
      (fields (field (name "MANUFACTURER PART NUMBER") "RC0603FR-073K9L") (field (name "TOLERANCE") "+-1%"))
      (libsource (lib "EMDO601_Patch") (part "3.9 kohm ±1% 0.1W"))
    )
    (comp (ref "R9")
      (value "20.5k")
      (footprint "R0603")
      (description "20.5 kohm ±1% 0.1W")
      (fields (field (name "MANUFACTURER PART NUMBER") "RC0603FR-0720K5L") (field (name "TOLERANCE") "+-1%"))
      (libsource (lib "EMDO601_Patch") (part "20.5 kohm ±1% 0.1W"))
    )
    (comp (ref "R10")
      (value "35.7k")
      (footprint "R0603")
      (description "35.7kohm ±1% 0.1W")
      (fields (field (name "MANUFACTURER PART NUMBER") "RC0603FR-0735K7L") (field (name "TOLERANCE") "+-1%"))
      (libsource (lib "EMDO601_Patch") (part "35.7kohm ±1% 0.1W"))
    )
    (comp (ref "R11")
      (value "5.1k")
      (footprint "R0603")
      (description "5.1kohm ±1% 0.1W")
      (fields (field (name "MANUFACTURER PART NUMBER") "RC0603FR-075K1L") (field (name "TOLERANCE") "+-1%"))
      (libsource (lib "EMDO601_Patch") (part "5.1kohm ±1% 0.1W"))
    )
    (comp (ref "R12")
      (value "2k")
      (footprint "R0603")
      (description "2 kohm ±1% 0.1W")
      (fields (field (name "MANUFACTURER PART NUMBER") "RC0603FR-072KL") (field (name "TOLERANCE") "+-1%"))
      (libsource (lib "EMDO601_Patch") (part "2 kohm ±1% 0.1W"))
    )
    (comp (ref "R13")
      (value "330k")
      (footprint "R0603")
      (description "330 kohm ±1% 0.1W")
      (fields (field (name "MANUFACTURER PART NUMBER") "RC0603FR-07330KL") (field (name "TOLERANCE") "+-1%"))
      (libsource (lib "EMDO601_Patch") (part "330 kohm ±1% 0.1W"))
    )
    (comp (ref "R14")
      (value "3.6k")
      (footprint "R0603")
      (description "3.6kohm ±1% 0.1W")
      (fields (field (name "MANUFACTURER PART NUMBER") "RC0603FR-073K6L") (field (name "TOLERANCE") "+-1%"))
      (libsource (lib "EMDO601_Patch") (part "3.6kohm ±1% 0.1W"))
    )
    (comp (ref "R15")
      (value "5.1k")
      (footprint "R0603")
      (description "5.1kohm ±1% 0.1W")
      (fields (field (name "MANUFACTURER PART NUMBER") "RC0603FR-075K1L") (field (name "TOLERANCE") "+-1%"))
      (libsource (lib "EMDO601_Patch") (part "5.1kohm ±1% 0.1W"))
    )
    (comp (ref "R16")
      (value "5.1k")
      (footprint "R0603")
      (description "5.1kohm ±1% 0.1W")
      (fields (field (name "MANUFACTURER PART NUMBER") "RC0603FR-075K1L") (field (name "TOLERANCE") "+-1%"))
      (libsource (lib "EMDO601_Patch") (part "5.1kohm ±1% 0.1W"))
    )
    (comp (ref "R17")
      (value "5.1k")
      (footprint "R0603")
      (description "5.1kohm ±1% 0.1W")
      (fields (field (name "MANUFACTURER PART NUMBER") "RC0603FR-075K1L") (field (name "TOLERANCE") "+-1%"))
      (libsource (lib "EMDO601_Patch") (part "5.1kohm ±1% 0.1W"))
    )
    (comp (ref "R18")
      (value "330k")
      (footprint "R0603")
      (description "330 kohm ±1% 0.1W")
      (fields (field (name "MANUFACTURER PART NUMBER") "RC0603FR-07330KL") (field (name "TOLERANCE") "+-1%"))
      (libsource (lib "EMDO601_Patch") (part "330 kohm ±1% 0.1W"))
    )
    (comp (ref "R19")
      (value "2.2R")
      (footprint "R0603")
      (description "0.1W/ 2.2 ohm±1%")
      (fields
        (field (name "MANUFACTURER PART NUMBER") "RC0603FR-072R2L")
        (field (name "MANUFACTURER") "Yageo")
      )
      (libsource (lib "RCL") (part "RES"))
    )
    (comp (ref "R20")
      (value "10k")
      (footprint "R0603")
      (description "0.1W/ 10kohm±1%")
      (fields
        (field (name "MANUFACTURER PART NUMBER") "RC0603FR-0710KL")
        (field (name "MANUFACTURER") "Yageo")
      )
      (libsource (lib "RCL") (part "RES"))
    )
    (comp (ref "R21")
      (value "2.2R")
      (footprint "R0603")
      (description "0.1W/ 2.2 ohm±1%")
      (fields
        (field (name "MANUFACTURER PART NUMBER") "RC0603FR-072R2L")
        (field (name "MANUFACTURER") "Yageo")
      )
      (libsource (lib "RCL") (part "RES"))
    )
    (comp (ref "R22")
      (value "10k")
      (footprint "R0603")
      (description "0.1W/ 10kohm±1%")
      (fields
        (field (name "MANUFACTURER PART NUMBER") "RC0603FR-0710KL")
        (field (name "MANUFACTURER") "Yageo")
      )
      (libsource (lib "RCL") (part "RES"))
    )
    (comp (ref "R23")
      (value "20R")
      (footprint "R0603")
      (description "0.1W/ 20 ohm±1%")
      (fields
        (field (name "MANUFACTURER PART NUMBER") "RC0603FR-0720RL")
        (field (name "MANUFACTURER") "Yageo")
      )
      (libsource (lib "RCL") (part "RES"))
    )
    (comp (ref "R24")
      (value "20R")
      (footprint "R0603")
      (description "0.1W/ 20 ohm±1%")
      (fields
        (field (name "MANUFACTURER PART NUMBER") "RC0603FR-0720RL")
        (field (name "MANUFACTURER") "Yageo")
      )
      (libsource (lib "RCL") (part "RES"))
    )
    (comp (ref "R25")
      (value "100k")
      (footprint "R0603")
      (description "100 kohm ±1% 0.1W")
      (fields (field (name "MANUFACTURER PART NUMBER") "RC0603FR-07100KL") (field (name "TOLERANCE") "+-1%"))
      (libsource (lib "EMDO601_Patch") (part "100 kohm ±1% 0.1W"))
    )
    (comp (ref "R26")
      (value "100k")
      (footprint "R0603")
      (description "100 kohm ±1% 0.1W")
      (fields (field (name "MANUFACTURER PART NUMBER") "RC0603FR-07100KL") (field (name "TOLERANCE") "+-1%"))
      (libsource (lib "EMDO601_Patch") (part "100 kohm ±1% 0.1W"))
    )
    (comp (ref "R27")
      (value "10R")
      (footprint "R0603")
      (description "10 ohm ±1% 0.1W")
      (fields (field (name "MANUFACTURER PART NUMBER") "RC0603FR-0710RL") (field (name "TOLERANCE") "+-1%"))
      (libsource (lib "EMDO601_Patch") (part "10 ohm ±1% 0.1W"))
    )
    (comp (ref "R28")
      (value "10R")
      (footprint "R0603")
      (description "10 ohm ±1% 0.1W")
      (fields (field (name "MANUFACTURER PART NUMBER") "RC0603FR-0710RL") (field (name "TOLERANCE") "+-1%"))
      (libsource (lib "EMDO601_Patch") (part "10 ohm ±1% 0.1W"))
    )
    (comp (ref "R29")
      (value "10k")
      (footprint "R0603")
      (description "10 kohm ±1% 0.1W")
      (fields (field (name "MANUFACTURER PART NUMBER") "RC0603FR-0710KL") (field (name "TOLERANCE") "+-1%"))
      (libsource (lib "EMDO601_Patch") (part "10 kohm ±1% 0.1W"))
    )
    (comp (ref "R30")
      (value "10k")
      (footprint "R0603")
      (description "10 kohm ±1% 0.1W")
      (fields (field (name "MANUFACTURER PART NUMBER") "RC0603FR-0710KL") (field (name "TOLERANCE") "+-1%"))
      (libsource (lib "EMDO601_Patch") (part "10 kohm ±1% 0.1W"))
    )
    (comp (ref "R31")
      (value "10R")
      (footprint "R0603")
      (description "10 ohm ±1% 0.1W")
      (fields (field (name "MANUFACTURER PART NUMBER") "RC0603FR-0710RL") (field (name "TOLERANCE") "+-1%"))
      (libsource (lib "EMDO601_Patch") (part "10 ohm ±1% 0.1W"))
    )
    (comp (ref "R32")
      (value "10R")
      (footprint "R0603")
      (description "10 ohm ±1% 0.1W")
      (fields (field (name "MANUFACTURER PART NUMBER") "RC0603FR-0710RL") (field (name "TOLERANCE") "+-1%"))
      (libsource (lib "EMDO601_Patch") (part "10 ohm ±1% 0.1W"))
    )
    (comp (ref "R33")
      (value "5.36k")
      (footprint "R0603")
      (description "0.1W/ 5.36kohm±1%")
      (fields
        (field (name "MANUFACTURER PART NUMBER") "RC0603FR-075K36L")
        (field (name "MANUFACTURER") "Yageo")
      )
      (libsource (lib "RCL") (part "RES"))
    )
    (comp (ref "R34")
      (value "5.36k")
      (footprint "R0603")
      (description "0.1W/ 5.36kohm±1%")
      (fields
        (field (name "MANUFACTURER PART NUMBER") "RC0603FR-075K36L")
        (field (name "MANUFACTURER") "Yageo")
      )
      (libsource (lib "RCL") (part "RES"))
    )
    (comp (ref "R35")
      (value "43.2k")
      (footprint "R0603")
      (description "0.1W/ 43.2kohm±1%")
      (fields
        (field (name "MANUFACTURER PART NUMBER") "RC0603FR-0743K2L")
        (field (name "MANUFACTURER") "Yageo")
      )
      (libsource (lib "RCL") (part "RES"))
    )
    (comp (ref "R36")
      (value "332k")
      (footprint "R0603")
      (description "0.1W/ 332kohm±1%")
      (fields
        (field (name "MANUFACTURER PART NUMBER") "RC0603FR-07332KL")
        (field (name "MANUFACTURER") "Yageo")
      )
      (libsource (lib "RCL") (part "RES"))
    )
    (comp (ref "R37")
      (value "43.2k")
      (footprint "R0603")
      (description "0.1W/ 43.2kohm±1%")
      (fields
        (field (name "MANUFACTURER PART NUMBER") "RC0603FR-0743K2L")
        (field (name "MANUFACTURER") "Yageo")
      )
      (libsource (lib "RCL") (part "RES"))
    )
    (comp (ref "R38")
      (value "332k")
      (footprint "R0603")
      (description "0.1W/ 332kohm±1%")
      (fields
        (field (name "MANUFACTURER PART NUMBER") "RC0603FR-07332KL")
        (field (name "MANUFACTURER") "Yageo")
      )
      (libsource (lib "RCL") (part "RES"))
    )
    (comp (ref "R39")
      (value "0.5R")
      (footprint "R1206")
      (description "0.5 ohm ±1% 0.5W")
      (fields
        (field (name "MANUFACTURER PART NUMBER") "CSR1206FKR500")
        (field (name "MANUFACTURER") "SEI Stackpole")
      )
      (libsource (lib "EMDO601_Patch") (part "0.5 ohm ±1% 0.5W"))
    )
    (comp (ref "R40")
      (value "180R")
      (footprint "R0603")
      (description "180 ohm ±1% 0.1W")
      (fields (field (name "MANUFACTURER PART NUMBER") "RC0603FR-07180RL") (field (name "TOLERANCE") "+-1%"))
      (libsource (lib "EMDO601_Patch") (part "180 ohm ±1% 0.1W"))
    )
    (comp (ref "R41")
      (value "7.87k")
      (footprint "R0603")
      (description "0.1W/ 7.87kohm±1%")
      (fields
        (field (name "MANUFACTURER PART NUMBER") "RC0603FR-077K87L")
        (field (name "MANUFACTURER") "Yageo")
      )
      (libsource (lib "RCL") (part "RES"))
    )
    (comp (ref "R42")
      (value "7.87k")
      (footprint "R0603")
      (description "0.1W/ 7.87kohm±1%")
      (fields
        (field (name "MANUFACTURER PART NUMBER") "RC0603FR-077K87L")
        (field (name "MANUFACTURER") "Yageo")
      )
      (libsource (lib "RCL") (part "RES"))
    )
    (comp (ref "R43")
      (value "47k")
      (footprint "R0603")
      (description "47 kohm ±1% 0.1W")
      (fields (field (name "MANUFACTURER PART NUMBER") "RC0603FR-0747KL") (field (name "TOLERANCE") "+-1%"))
      (libsource (lib "EMDO601_Patch") (part "47 kohm ±1% 0.1W"))
    )
    (comp (ref "R44")
      (value "51k")
      (footprint "R0603")
      (description "0.1W/ 51kohm±1%")
      (fields
        (field (name "MANUFACTURER PART NUMBER") "RC0603FR-0751KL")
        (field (name "MANUFACTURER") "Yageo")
      )
      (libsource (lib "RCL") (part "RES"))
    )
    (comp (ref "R45")
      (value "51k")
      (footprint "R0603")
      (description "0.1W/ 51kohm±1%")
      (fields
        (field (name "MANUFACTURER PART NUMBER") "RC0603FR-0751KL")
        (field (name "MANUFACTURER") "Yageo")
      )
      (libsource (lib "RCL") (part "RES"))
    )
    (comp (ref "R46")
      (value "6.98k")
      (footprint "R0603")
      (description "6.98kohm ±1% 0.1W")
      (fields
        (field (name "MANUFACTURER PART NUMBER") "RC0603FR-076K98L")
        (field (name "MANUFACTURER") "Yageo")
      )
      (libsource (lib "EMDO601_Patch") (part "6.98kohm ±1% 0.1W"))
    )
    (comp (ref "R47")
      (value "3k")
      (footprint "R0603")
      (description "3kohm ±1% 0.1W")
      (fields
        (field (name "MANUFACTURER PART NUMBER") "RC0603FR-073KL")
        (field (name "MANUFACTURER") "Yageo")
      )
      (libsource (lib "EMDO601_Patch") (part "3kohm ±1% 0.1W"))
    )
    (comp (ref "R48")
      (value "2.2k")
      (footprint "R0603")
      (description "2.2 kohm ±1% 0.1W")
      (fields (field (name "MANUFACTURER PART NUMBER") "RC0603FR-072K2L") (field (name "TOLERANCE") "+-1%"))
      (libsource (lib "EMDO601_Patch") (part "2.2 kohm ±1% 0.1W"))
    )
    (comp (ref "R49")
      (value "1k")
      (footprint "R0603")
      (description "0.1W/ 1kohm±1%")
      (fields
        (field (name "MANUFACTURER PART NUMBER") "RC0603FR-071KL")
        (field (name "MANUFACTURER") "Yageo")
      )
      (libsource (lib "RCL") (part "RES"))
    )
    (comp (ref "R50")
      (value "1k")
      (footprint "R0603")
      (description "0.1W/ 1kohm±1%")
      (fields
        (field (name "MANUFACTURER PART NUMBER") "RC0603FR-071KL")
        (field (name "MANUFACTURER") "Yageo")
      )
      (libsource (lib "RCL") (part "RES"))
    )
    (comp (ref "TIM1")
      (value "PL-1-5-76X127-60")
      (fields (field (name "MANUFACTURER") "Wakefield-Vette"))
      (libsource (lib "EMDO601_Patch") (part "PL-1-5-76X127-60"))
    )
    (comp (ref "U1")
      (value "LM5060Q1MMX/NOPB")
      (footprint "MSOP-10")
      (fields (field (name "MANUFACTURER") "Texas Instruments"))
      (libsource (lib "EMDO601_Patch") (part "LM5060Q1MMX/NOPB"))
    )
    (comp (ref "U2")
      (value "LM5060Q1MMX/NOPB")
      (footprint "MSOP-10")
      (fields (field (name "MANUFACTURER") "Texas Instruments"))
      (libsource (lib "") (part "LM5060Q1MMX/NOPB_1"))
    )
    (comp (ref "U3")
      (value "LM5108DRCT")
      (footprint "VSON-10")
      (description "Gate Drivers 2.6-A, 110-V half bridge gate driver with enable and interlock 10-VSON -40 to 125")
      (fields (field (name "MANUFACTURER") "Texas Instruments"))
      (libsource (lib "EMDO601_Patch") (part "LM5108DRCT"))
    )
    (comp (ref "U4")
      (value "INA240A2QDRQ1")
      (footprint "SOIC-8")
      (fields (field (name "MANUFACTURER") "Texas Instruments"))
      (libsource (lib "EMDO601_Patch") (part "INA240A2QDRQ1"))
    )
    (comp (ref "U5")
      (value "INA240A2QDRQ1")
      (footprint "SOIC-8")
      (fields (field (name "MANUFACTURER") "Texas Instruments"))
      (libsource (lib "EMDO601_Patch") (part "INA240A2QDRQ1"))
    )
    (comp (ref "U6")
      (value "LM5018MR/NOPB")
      (footprint "SOIC-8(EPAD)")
      (description "7.5-100V Wide Vin, 300mA Constant On-Time Synchronous Buck Regulator 8-SO PowerPAD -40 to 125")
      (fields (field (name "MANUFACTURER") "Texas Instruments"))
      (libsource (lib "EMDO601_Patch") (part "LM5018MR/NOPB"))
    )
    (comp (ref "U7")
      (value "LM5018MR/NOPB")
      (footprint "SOIC-8(EPAD)")
      (description "7.5-100V Wide Vin, 300mA Constant On-Time Synchronous Buck Regulator 8-SO PowerPAD -40 to 125")
      (fields (field (name "MANUFACTURER") "Texas Instruments"))
      (libsource (lib "EMDO601_Patch") (part "LM5018MR/NOPB"))
    )
    (comp (ref "U8")
      (value "MC33063AQDRQ1")
      (footprint "SOIC-8")
      (description "Switching Voltage Regulators 1.5-A Peak Boost/ Buck/Inverting")
      (fields (field (name "MANUFACTURER") "Texas Instruments"))
      (libsource (lib "EMDO601_Patch") (part "MC33063AQDRQ1"))
    )
    (comp (ref "U9")
      (value "REF3133AIDBZTG4")
      (footprint "SOT23-3")
      (description "3.3-V, 20-ppm/C max, 100-A, 3-pin SOT-23 series voltage reference 3-SOT-23 -40 to 125")
      (fields (field (name "MANUFACTURER") "Texas Instruments"))
      (libsource (lib "EMDO601_Patch") (part "REF3133AIDBZTG4"))
    )
    (comp (ref "Vsns_12V")
      (value "NO FIT")
      (footprint "TP_1")
      (description "Testpoint")
      (fields
        (field (name "MANUFACTURER") "None")
        (field (name "MANUFACTURER PART NUMBER") "Testpads, do not populate")
      )
      (libsource (lib "EnergyMeter") (part "TP"))
    )
    (comp (ref "Vsns_48V")
      (value "NO FIT")
      (footprint "TP_1")
      (description "Testpoint")
      (fields
        (field (name "MANUFACTURER") "None")
        (field (name "MANUFACTURER PART NUMBER") "Testpads, do not populate")
      )
      (libsource (lib "EnergyMeter") (part "TP"))
    )
  )
  (nets
    (net (code "1") (name "+5V") (class "Default")
      (node (ref "+5V") (pin "1") (pinfunction "TCT_1") (pintype "passive"))
      (node (ref "C29") (pin "2") (pinfunction "2_2") (pintype "passive"))
      (node (ref "C30") (pin "2") (pinfunction "2_2") (pintype "passive"))
      (node (ref "C48") (pin "1") (pinfunction "1_1") (pintype "passive"))
      (node (ref "C49") (pin "2") (pinfunction "2_2") (pintype "passive"))
      (node (ref "C53") (pin "2") (pinfunction "2_2") (pintype "passive"))
      (node (ref "L6") (pin "2") (pinfunction "2_2") (pintype "passive"))
      (node (ref "R47") (pin "2") (pinfunction "2_2") (pintype "passive"))
      (node (ref "U4") (pin "6") (pinfunction "VS_6") (pintype "passive"))
      (node (ref "U5") (pin "6") (pinfunction "VS_6") (pintype "passive"))
      (node (ref "U9") (pin "1") (pinfunction "IN_1") (pintype "power_in"))
    )
    (net (code "2") (name "+10V") (class "Default")
      (node (ref "+10V") (pin "1") (pinfunction "TCT_1") (pintype "passive"))
      (node (ref "C25") (pin "2") (pinfunction "2_2") (pintype "passive"))
      (node (ref "C46") (pin "1") (pinfunction "1_1") (pintype "passive"))
      (node (ref "C47") (pin "2") (pinfunction "2_2") (pintype "passive"))
      (node (ref "L5") (pin "2") (pinfunction "2_2") (pintype "passive"))
      (node (ref "R46") (pin "2") (pinfunction "2_2") (pintype "passive"))
      (node (ref "U3") (pin "1") (pinfunction "VDD_1") (pintype "passive"))
      (node (ref "U3") (pin "6") (pinfunction "EN_6") (pintype "passive"))
    )
    (net (code "3") (name "+12V") (class "Default")
      (node (ref "C43") (pin "2") (pinfunction "2_2") (pintype "passive"))
      (node (ref "D7") (pin "A") (pinfunction "A_A") (pintype "passive"))
      (node (ref "Q12") (pin "D") (pinfunction "D_D") (pintype "passive"))
      (node (ref "Q2") (pin "D") (pinfunction "D_D") (pintype "passive"))
      (node (ref "Q6") (pin "D") (pinfunction "D_D") (pintype "passive"))
      (node (ref "R10") (pin "2") (pinfunction "2_2") (pintype "passive"))
      (node (ref "R24") (pin "1") (pinfunction "1_1") (pintype "passive"))
      (node (ref "R39") (pin "1") (pinfunction "1_1") (pintype "passive"))
      (node (ref "R8") (pin "2") (pinfunction "2_2") (pintype "passive"))
      (node (ref "R9") (pin "2") (pinfunction "2_2") (pintype "passive"))
      (node (ref "U8") (pin "6") (pinfunction "VCC_6") (pintype "power_in"))
    )
    (net (code "4") (name "+48V") (class "Default")
      (node (ref "D1") (pin "A") (pinfunction "A_A") (pintype "passive"))
      (node (ref "D13") (pin "A") (pinfunction "A_A") (pintype "passive"))
      (node (ref "Q3") (pin "D") (pinfunction "D_D") (pintype "passive"))
      (node (ref "R2") (pin "2") (pinfunction "2_2") (pintype "passive"))
      (node (ref "R23") (pin "1") (pinfunction "1_1") (pintype "passive"))
      (node (ref "R3") (pin "2") (pinfunction "2_2") (pintype "passive"))
      (node (ref "R4") (pin "2") (pinfunction "2_2") (pintype "passive"))
    )
    (net (code "5") (name "/12V_EN") (class "Default")
      (node (ref "U2") (pin "5") (pinfunction "EN_5") (pintype "passive"))
    )
    (net (code "6") (name "/48V_EN") (class "Default")
      (node (ref "U1") (pin "5") (pinfunction "EN_5") (pintype "passive"))
    )
    (net (code "7") (name "/BG") (class "Default")
      (node (ref "Q13") (pin "G") (pinfunction "G_G") (pintype "passive"))
      (node (ref "Q14") (pin "G") (pinfunction "G_G") (pintype "passive"))
      (node (ref "Q15") (pin "G") (pinfunction "G_G") (pintype "passive"))
      (node (ref "U3") (pin "10") (pinfunction "LO_10") (pintype "passive"))
    )
    (net (code "8") (name "/Isns_12V") (class "Default")
      (node (ref "C34") (pin "2") (pinfunction "2_2") (pintype "passive"))
      (node (ref "Isns_12V") (pin "1") (pinfunction "TCT_1") (pintype "passive"))
      (node (ref "R30") (pin "2") (pinfunction "2_2") (pintype "passive"))
    )
    (net (code "9") (name "/Isns_48V") (class "Default")
      (node (ref "C33") (pin "2") (pinfunction "2_2") (pintype "passive"))
      (node (ref "Isns_48V") (pin "1") (pinfunction "TCT_1") (pintype "passive"))
      (node (ref "R29") (pin "2") (pinfunction "2_2") (pintype "passive"))
    )
    (net (code "10") (name "/PWMH") (class "Default")
      (node (ref "PWMH") (pin "1") (pinfunction "TCT_1") (pintype "passive"))
      (node (ref "R19") (pin "1") (pinfunction "1_1") (pintype "passive"))
    )
    (net (code "11") (name "/PWML") (class "Default")
      (node (ref "PWML") (pin "1") (pinfunction "TCT_1") (pintype "passive"))
      (node (ref "R21") (pin "1") (pinfunction "1_1") (pintype "passive"))
    )
    (net (code "12") (name "/SNS1N") (class "Default")
      (node (ref "C1") (pin "1") (pinfunction "1_1") (pintype "passive"))
      (node (ref "C2") (pin "1") (pinfunction "1_1") (pintype "passive"))
      (node (ref "C3") (pin "1") (pinfunction "1_1") (pintype "passive"))
      (node (ref "C4") (pin "1") (pinfunction "1_1") (pintype "passive"))
      (node (ref "Q7") (pin "D") (pinfunction "D_D") (pintype "passive"))
      (node (ref "Q8") (pin "D") (pinfunction "D_D") (pintype "passive"))
      (node (ref "Q9") (pin "D") (pinfunction "D_D") (pintype "passive"))
      (node (ref "R1") (pin "2") (pinfunction "2_2") (pintype "passive"))
      (node (ref "R31") (pin "1") (pinfunction "1_1") (pintype "passive"))
    )
    (net (code "13") (name "/SNS1P") (class "Default")
      (node (ref "C10") (pin "1") (pinfunction "1_1") (pintype "passive"))
      (node (ref "C11") (pin "1") (pinfunction "1_1") (pintype "passive"))
      (node (ref "C12") (pin "1") (pinfunction "1_1") (pintype "passive"))
      (node (ref "L1") (pin "2") (pinfunction "2_2") (pintype "passive"))
      (node (ref "R1") (pin "1") (pinfunction "1_1") (pintype "passive"))
      (node (ref "R27") (pin "1") (pinfunction "1_1") (pintype "passive"))
    )
    (net (code "14") (name "/SNS2N") (class "Default")
      (node (ref "C13") (pin "1") (pinfunction "1_1") (pintype "passive"))
      (node (ref "C14") (pin "1") (pinfunction "1_1") (pintype "passive"))
      (node (ref "C18") (pin "1") (pinfunction "1_1") (pintype "passive"))
      (node (ref "C19") (pin "1") (pinfunction "1_1") (pintype "passive"))
      (node (ref "C20") (pin "1") (pinfunction "1_1") (pintype "passive"))
      (node (ref "C5") (pin "1") (pinfunction "1_1") (pintype "passive"))
      (node (ref "C6") (pin "1") (pinfunction "1_1") (pintype "passive"))
      (node (ref "L3") (pin "1") (pinfunction "1_1") (pintype "passive"))
      (node (ref "R32") (pin "1") (pinfunction "1_1") (pintype "passive"))
      (node (ref "R6") (pin "2") (pinfunction "2_2") (pintype "passive"))
    )
    (net (code "15") (name "/SNS2P") (class "Default")
      (node (ref "L2") (pin "2") (pinfunction "2_2") (pintype "passive"))
      (node (ref "R28") (pin "1") (pinfunction "1_1") (pintype "passive"))
      (node (ref "R6") (pin "1") (pinfunction "1_1") (pintype "passive"))
    )
    (net (code "16") (name "/SW") (class "Default")
      (node (ref "C27") (pin "1") (pinfunction "1_1") (pintype "passive"))
      (node (ref "L2") (pin "1") (pinfunction "1_1") (pintype "passive"))
      (node (ref "Q13") (pin "D") (pinfunction "D_D") (pintype "passive"))
      (node (ref "Q14") (pin "D") (pinfunction "D_D") (pintype "passive"))
      (node (ref "Q15") (pin "D") (pinfunction "D_D") (pintype "passive"))
      (node (ref "Q7") (pin "S") (pinfunction "S_S") (pintype "passive"))
      (node (ref "Q8") (pin "S") (pinfunction "S_S") (pintype "passive"))
      (node (ref "Q9") (pin "S") (pinfunction "S_S") (pintype "passive"))
      (node (ref "U3") (pin "5") (pinfunction "HS_5") (pintype "passive"))
    )
    (net (code "17") (name "/TG") (class "Default")
      (node (ref "Q7") (pin "G") (pinfunction "G_G") (pintype "passive"))
      (node (ref "Q8") (pin "G") (pinfunction "G_G") (pintype "passive"))
      (node (ref "Q9") (pin "G") (pinfunction "G_G") (pintype "passive"))
      (node (ref "U3") (pin "4") (pinfunction "HO_4") (pintype "passive"))
    )
    (net (code "18") (name "/Vsns_12V") (class "Default")
      (node (ref "R26") (pin "1") (pinfunction "1_1") (pintype "passive"))
      (node (ref "R34") (pin "1") (pinfunction "1_1") (pintype "passive"))
      (node (ref "Vsns_12V") (pin "1") (pinfunction "TCT_1") (pintype "passive"))
    )
    (net (code "19") (name "/Vsns_48V") (class "Default")
      (node (ref "R25") (pin "1") (pinfunction "1_1") (pintype "passive"))
      (node (ref "R33") (pin "1") (pinfunction "1_1") (pintype "passive"))
      (node (ref "Vsns_48V") (pin "1") (pinfunction "TCT_1") (pintype "passive"))
    )
    (net (code "20") (name "3V3_REF") (class "Default")
      (node (ref "C35") (pin "2") (pinfunction "2_2") (pintype "passive"))
      (node (ref "C36") (pin "2") (pinfunction "2_2") (pintype "passive"))
      (node (ref "C54") (pin "2") (pinfunction "2_2") (pintype "passive"))
      (node (ref "U4") (pin "7") (pinfunction "REF1_7") (pintype "passive"))
      (node (ref "U5") (pin "7") (pinfunction "REF1_7") (pintype "passive"))
      (node (ref "U9") (pin "2") (pinfunction "OUT_2") (pintype "output"))
    )
    (net (code "21") (name "GND") (class "Default")
      (node (ref "C1") (pin "2") (pinfunction "2_2") (pintype "passive"))
      (node (ref "C10") (pin "2") (pinfunction "2_2") (pintype "passive"))
      (node (ref "C11") (pin "2") (pinfunction "2_2") (pintype "passive"))
      (node (ref "C12") (pin "2") (pinfunction "2_2") (pintype "passive"))
      (node (ref "C13") (pin "2") (pinfunction "2_2") (pintype "passive"))
      (node (ref "C14") (pin "2") (pinfunction "2_2") (pintype "passive"))
      (node (ref "C15") (pin "2") (pinfunction "2_2") (pintype "passive"))
      (node (ref "C16") (pin "2") (pinfunction "2_2") (pintype "passive"))
      (node (ref "C17") (pin "2") (pinfunction "2_2") (pintype "passive"))
      (node (ref "C18") (pin "2") (pinfunction "2_2") (pintype "passive"))
      (node (ref "C19") (pin "2") (pinfunction "2_2") (pintype "passive"))
      (node (ref "C2") (pin "2") (pinfunction "2_2") (pintype "passive"))
      (node (ref "C20") (pin "2") (pinfunction "2_2") (pintype "passive"))
      (node (ref "C21") (pin "1") (pinfunction "1_1") (pintype "passive"))
      (node (ref "C22") (pin "1") (pinfunction "1_1") (pintype "passive"))
      (node (ref "C23") (pin "1") (pinfunction "1_1") (pintype "passive"))
      (node (ref "C24") (pin "1") (pinfunction "1_1") (pintype "passive"))
      (node (ref "C25") (pin "1") (pinfunction "1_1") (pintype "passive"))
      (node (ref "C26") (pin "2") (pinfunction "2_2") (pintype "passive"))
      (node (ref "C28") (pin "2") (pinfunction "2_2") (pintype "passive"))
      (node (ref "C29") (pin "1") (pinfunction "1_1") (pintype "passive"))
      (node (ref "C3") (pin "2") (pinfunction "2_2") (pintype "passive"))
      (node (ref "C30") (pin "1") (pinfunction "1_1") (pintype "passive"))
      (node (ref "C33") (pin "1") (pinfunction "1_1") (pintype "passive"))
      (node (ref "C34") (pin "1") (pinfunction "1_1") (pintype "passive"))
      (node (ref "C35") (pin "1") (pinfunction "1_1") (pintype "passive"))
      (node (ref "C36") (pin "1") (pinfunction "1_1") (pintype "passive"))
      (node (ref "C37") (pin "1") (pinfunction "1_1") (pintype "passive"))
      (node (ref "C38") (pin "1") (pinfunction "1_1") (pintype "passive"))
      (node (ref "C39") (pin "1") (pinfunction "1_1") (pintype "passive"))
      (node (ref "C4") (pin "2") (pinfunction "2_2") (pintype "passive"))
      (node (ref "C40") (pin "1") (pinfunction "1_1") (pintype "passive"))
      (node (ref "C43") (pin "1") (pinfunction "1_1") (pintype "passive"))
      (node (ref "C44") (pin "1") (pinfunction "1_1") (pintype "passive"))
      (node (ref "C45") (pin "2") (pinfunction "2_2") (pintype "passive"))
      (node (ref "C47") (pin "1") (pinfunction "1_1") (pintype "passive"))
      (node (ref "C49") (pin "1") (pinfunction "1_1") (pintype "passive"))
      (node (ref "C5") (pin "2") (pinfunction "2_2") (pintype "passive"))
      (node (ref "C52") (pin "1") (pinfunction "1_1") (pintype "passive"))
      (node (ref "C53") (pin "1") (pinfunction "1_1") (pintype "passive"))
      (node (ref "C54") (pin "1") (pinfunction "1_1") (pintype "passive"))
      (node (ref "C6") (pin "2") (pinfunction "2_2") (pintype "passive"))
      (node (ref "C7") (pin "2") (pinfunction "2_2") (pintype "passive"))
      (node (ref "C8") (pin "2") (pinfunction "2_2") (pintype "passive"))
      (node (ref "C9") (pin "2") (pinfunction "2_2") (pintype "passive"))
      (node (ref "D10") (pin "1") (pinfunction "A_1") (pintype "passive"))
      (node (ref "D12") (pin "1") (pinfunction "A_1") (pintype "passive"))
      (node (ref "D5") (pin "1") (pinfunction "A_1") (pintype "passive"))
      (node (ref "D9") (pin "1") (pinfunction "A_1") (pintype "passive"))
      (node (ref "Q13") (pin "S") (pinfunction "S_S") (pintype "passive"))
      (node (ref "Q14") (pin "S") (pinfunction "S_S") (pintype "passive"))
      (node (ref "Q15") (pin "S") (pinfunction "S_S") (pintype "passive"))
      (node (ref "R13") (pin "1") (pinfunction "1_1") (pintype "passive"))
      (node (ref "R14") (pin "1") (pinfunction "1_1") (pintype "passive"))
      (node (ref "R15") (pin "1") (pinfunction "1_1") (pintype "passive"))
      (node (ref "R16") (pin "1") (pinfunction "1_1") (pintype "passive"))
      (node (ref "R17") (pin "1") (pinfunction "1_1") (pintype "passive"))
      (node (ref "R18") (pin "1") (pinfunction "1_1") (pintype "passive"))
      (node (ref "R20") (pin "1") (pinfunction "1_1") (pintype "passive"))
      (node (ref "R22") (pin "1") (pinfunction "1_1") (pintype "passive"))
      (node (ref "R33") (pin "2") (pinfunction "2_2") (pintype "passive"))
      (node (ref "R34") (pin "2") (pinfunction "2_2") (pintype "passive"))
      (node (ref "R41") (pin "2") (pinfunction "2_2") (pintype "passive"))
      (node (ref "R42") (pin "2") (pinfunction "2_2") (pintype "passive"))
      (node (ref "R48") (pin "1") (pinfunction "1_1") (pintype "passive"))
      (node (ref "R49") (pin "2") (pinfunction "2_2") (pintype "passive"))
      (node (ref "R50") (pin "2") (pinfunction "2_2") (pintype "passive"))
      (node (ref "U1") (pin "6") (pinfunction "GND_6") (pintype "passive"))
      (node (ref "U2") (pin "6") (pinfunction "GND_6") (pintype "passive"))
      (node (ref "U3") (pin "11") (pinfunction "PAD_11") (pintype "passive"))
      (node (ref "U3") (pin "9") (pinfunction "VSS_9") (pintype "passive"))
      (node (ref "U4") (pin "2") (pinfunction "GND_2") (pintype "passive"))
      (node (ref "U4") (pin "3") (pinfunction "REF2_3") (pintype "passive"))
      (node (ref "U5") (pin "2") (pinfunction "GND_2") (pintype "passive"))
      (node (ref "U5") (pin "3") (pinfunction "REF2_3") (pintype "passive"))
      (node (ref "U6") (pin "1") (pinfunction "GND_1") (pintype "passive"))
      (node (ref "U6") (pin "9") (pinfunction "PAD_9") (pintype "passive"))
      (node (ref "U7") (pin "1") (pinfunction "GND_1") (pintype "passive"))
      (node (ref "U7") (pin "9") (pinfunction "PAD_9") (pintype "passive"))
      (node (ref "U8") (pin "2") (pinfunction "SE_2") (pintype "power_in"))
      (node (ref "U8") (pin "4") (pinfunction "GND_4") (pintype "power_in"))
      (node (ref "U9") (pin "3") (pinfunction "GND_3") (pintype "passive"))
    )
    (net (code "22") (name "Net-(C7-Pad1)") (class "Default")
      (node (ref "C7") (pin "1") (pinfunction "1_1") (pintype "passive"))
      (node (ref "C8") (pin "1") (pinfunction "1_1") (pintype "passive"))
      (node (ref "C9") (pin "1") (pinfunction "1_1") (pintype "passive"))
      (node (ref "D2") (pin "A") (pinfunction "A_A") (pintype "passive"))
      (node (ref "L1") (pin "1") (pinfunction "1_1") (pintype "passive"))
      (node (ref "Q4") (pin "D") (pinfunction "D_D") (pintype "passive"))
      (node (ref "R5") (pin "2") (pinfunction "2_2") (pintype "passive"))
    )
    (net (code "23") (name "Net-(C15-Pad1)") (class "Default")
      (node (ref "C15") (pin "1") (pinfunction "1_1") (pintype "passive"))
      (node (ref "C16") (pin "1") (pinfunction "1_1") (pintype "passive"))
      (node (ref "C17") (pin "1") (pinfunction "1_1") (pintype "passive"))
      (node (ref "D6") (pin "A") (pinfunction "A_A") (pintype "passive"))
      (node (ref "L3") (pin "2") (pinfunction "2_2") (pintype "passive"))
      (node (ref "Q1") (pin "D") (pinfunction "D_D") (pintype "passive"))
      (node (ref "Q11") (pin "D") (pinfunction "D_D") (pintype "passive"))
      (node (ref "Q5") (pin "D") (pinfunction "D_D") (pintype "passive"))
      (node (ref "R11") (pin "2") (pinfunction "2_2") (pintype "passive"))
    )
    (net (code "24") (name "Net-(C46-Pad2)") (class "Default")
      (node (ref "C46") (pin "2") (pinfunction "2_2") (pintype "passive"))
      (node (ref "C50") (pin "2") (pinfunction "2_2") (pintype "passive"))
      (node (ref "R44") (pin "2") (pinfunction "2_2") (pintype "passive"))
    )
    (net (code "25") (name "Net-(C48-Pad2)") (class "Default")
      (node (ref "C48") (pin "2") (pinfunction "2_2") (pintype "passive"))
      (node (ref "C51") (pin "2") (pinfunction "2_2") (pintype "passive"))
      (node (ref "R45") (pin "2") (pinfunction "2_2") (pintype "passive"))
    )
    (net (code "26") (name "Net-(D3-K)") (class "Default")
      (node (ref "D3") (pin "C") (pinfunction "K_C") (pintype "passive"))
      (node (ref "R7") (pin "1") (pinfunction "1_1") (pintype "passive"))
      (node (ref "U1") (pin "10") (pinfunction "GATE_10") (pintype "passive"))
    )
    (net (code "27") (name "Net-(D4-K)") (class "Default")
      (node (ref "D4") (pin "C") (pinfunction "K_C") (pintype "passive"))
      (node (ref "Q10") (pin "1") (pinfunction "B_1") (pintype "passive"))
      (node (ref "R13") (pin "2") (pinfunction "2_2") (pintype "passive"))
    )
    (net (code "28") (name "Net-(D5-C)") (class "Default")
      (node (ref "D5") (pin "3") (pinfunction "C_3") (pintype "passive"))
      (node (ref "R2") (pin "1") (pinfunction "1_1") (pintype "passive"))
      (node (ref "U1") (pin "1") (pinfunction "SEN_1") (pintype "passive"))
    )
    (net (code "29") (name "Net-(D8-K)") (class "Default")
      (node (ref "D8") (pin "C") (pinfunction "K_C") (pintype "passive"))
      (node (ref "R12") (pin "2") (pinfunction "2_2") (pintype "passive"))
      (node (ref "U2") (pin "10") (pinfunction "GATE_10") (pintype "passive"))
    )
    (net (code "30") (name "Net-(D9-C)") (class "Default")
      (node (ref "D9") (pin "3") (pinfunction "C_3") (pintype "passive"))
      (node (ref "R8") (pin "1") (pinfunction "1_1") (pintype "passive"))
      (node (ref "U2") (pin "1") (pinfunction "SEN_1") (pintype "passive"))
    )
    (net (code "31") (name "Net-(D10-C)") (class "Default")
      (node (ref "C21") (pin "2") (pinfunction "2_2") (pintype "passive"))
      (node (ref "D1") (pin "C") (pinfunction "C_C") (pintype "passive"))
      (node (ref "D10") (pin "3") (pinfunction "C_3") (pintype "passive"))
      (node (ref "D2") (pin "C") (pinfunction "C_C") (pintype "passive"))
      (node (ref "U1") (pin "2") (pinfunction "VIN_2") (pintype "passive"))
    )
    (net (code "32") (name "Net-(D11-K)") (class "Default")
      (node (ref "D11") (pin "C") (pinfunction "K_C") (pintype "passive"))
      (node (ref "Q16") (pin "1") (pinfunction "B_1") (pintype "passive"))
      (node (ref "R18") (pin "2") (pinfunction "2_2") (pintype "passive"))
    )
    (net (code "33") (name "Net-(D12-C)") (class "Default")
      (node (ref "C24") (pin "2") (pinfunction "2_2") (pintype "passive"))
      (node (ref "D12") (pin "3") (pinfunction "C_3") (pintype "passive"))
      (node (ref "D6") (pin "C") (pinfunction "C_C") (pintype "passive"))
      (node (ref "D7") (pin "C") (pinfunction "C_C") (pintype "passive"))
      (node (ref "U2") (pin "2") (pinfunction "VIN_2") (pintype "passive"))
    )
    (net (code "34") (name "Net-(Q10-C)") (class "Default")
      (node (ref "D3") (pin "A") (pinfunction "A_A") (pintype "passive"))
      (node (ref "Q10") (pin "3") (pinfunction "C_3") (pintype "passive"))
      (node (ref "Q3") (pin "G") (pinfunction "G_G") (pintype "passive"))
      (node (ref "Q4") (pin "G") (pinfunction "G_G") (pintype "passive"))
      (node (ref "R7") (pin "2") (pinfunction "2_2") (pintype "passive"))
    )
    (net (code "35") (name "Net-(Q10-E)") (class "Default")
      (node (ref "D4") (pin "A") (pinfunction "A_A") (pintype "passive"))
      (node (ref "Q10") (pin "2") (pinfunction "E_2") (pintype "passive"))
      (node (ref "Q3") (pin "S") (pinfunction "S_S") (pintype "passive"))
      (node (ref "Q4") (pin "S") (pinfunction "S_S") (pintype "passive"))
    )
    (net (code "36") (name "Net-(Q16-C)") (class "Default")
      (node (ref "D8") (pin "A") (pinfunction "A_A") (pintype "passive"))
      (node (ref "Q1") (pin "G") (pinfunction "G_G") (pintype "passive"))
      (node (ref "Q11") (pin "G") (pinfunction "G_G") (pintype "passive"))
      (node (ref "Q12") (pin "G") (pinfunction "G_G") (pintype "passive"))
      (node (ref "Q16") (pin "3") (pinfunction "C_3") (pintype "passive"))
      (node (ref "Q2") (pin "G") (pinfunction "G_G") (pintype "passive"))
      (node (ref "Q5") (pin "G") (pinfunction "G_G") (pintype "passive"))
      (node (ref "Q6") (pin "G") (pinfunction "G_G") (pintype "passive"))
      (node (ref "R12") (pin "1") (pinfunction "1_1") (pintype "passive"))
    )
    (net (code "37") (name "Net-(Q16-E)") (class "Default")
      (node (ref "D11") (pin "A") (pinfunction "A_A") (pintype "passive"))
      (node (ref "Q1") (pin "S") (pinfunction "S_S") (pintype "passive"))
      (node (ref "Q11") (pin "S") (pinfunction "S_S") (pintype "passive"))
      (node (ref "Q12") (pin "S") (pinfunction "S_S") (pintype "passive"))
      (node (ref "Q16") (pin "2") (pinfunction "E_2") (pintype "passive"))
      (node (ref "Q2") (pin "S") (pinfunction "S_S") (pintype "passive"))
      (node (ref "Q5") (pin "S") (pinfunction "S_S") (pintype "passive"))
      (node (ref "Q6") (pin "S") (pinfunction "S_S") (pintype "passive"))
    )
    (net (code "38") (name "Net-(R23-Pad2)") (class "Default")
      (node (ref "R23") (pin "2") (pinfunction "2_2") (pintype "passive"))
      (node (ref "R25") (pin "2") (pinfunction "2_2") (pintype "passive"))
    )
    (net (code "39") (name "Net-(R24-Pad2)") (class "Default")
      (node (ref "R24") (pin "2") (pinfunction "2_2") (pintype "passive"))
      (node (ref "R26") (pin "2") (pinfunction "2_2") (pintype "passive"))
    )
    (net (code "40") (name "Net-(U1-OUT)") (class "Default")
      (node (ref "R5") (pin "1") (pinfunction "1_1") (pintype "passive"))
      (node (ref "U1") (pin "9") (pinfunction "OUT_9") (pintype "passive"))
    )
    (net (code "41") (name "Net-(U1-OVP)") (class "Default")
      (node (ref "R14") (pin "2") (pinfunction "2_2") (pintype "passive"))
      (node (ref "R3") (pin "1") (pinfunction "1_1") (pintype "passive"))
      (node (ref "U1") (pin "3") (pinfunction "OVP_3") (pintype "passive"))
    )
    (net (code "42") (name "Net-(U1-TIMER)") (class "Default")
      (node (ref "C22") (pin "2") (pinfunction "2_2") (pintype "passive"))
      (node (ref "U1") (pin "7") (pinfunction "TIMER_7") (pintype "passive"))
    )
    (net (code "43") (name "Net-(U1-UVLO)") (class "Default")
      (node (ref "R15") (pin "2") (pinfunction "2_2") (pintype "passive"))
      (node (ref "R4") (pin "1") (pinfunction "1_1") (pintype "passive"))
      (node (ref "U1") (pin "4") (pinfunction "UVLO_4") (pintype "passive"))
    )
    (net (code "44") (name "Net-(U2-OUT)") (class "Default")
      (node (ref "R11") (pin "1") (pinfunction "1_1") (pintype "passive"))
      (node (ref "U2") (pin "9") (pinfunction "OUT_9") (pintype "passive"))
    )
    (net (code "45") (name "Net-(U2-OVP)") (class "Default")
      (node (ref "R10") (pin "1") (pinfunction "1_1") (pintype "passive"))
      (node (ref "R17") (pin "2") (pinfunction "2_2") (pintype "passive"))
      (node (ref "U2") (pin "3") (pinfunction "OVP_3") (pintype "passive"))
    )
    (net (code "46") (name "Net-(U2-TIMER)") (class "Default")
      (node (ref "C23") (pin "2") (pinfunction "2_2") (pintype "passive"))
      (node (ref "U2") (pin "7") (pinfunction "TIMER_7") (pintype "passive"))
    )
    (net (code "47") (name "Net-(U2-UVLO)") (class "Default")
      (node (ref "R16") (pin "2") (pinfunction "2_2") (pintype "passive"))
      (node (ref "R9") (pin "1") (pinfunction "1_1") (pintype "passive"))
      (node (ref "U2") (pin "4") (pinfunction "UVLO_4") (pintype "passive"))
    )
    (net (code "48") (name "Net-(U3-HB)") (class "Default")
      (node (ref "C27") (pin "2") (pinfunction "2_2") (pintype "passive"))
      (node (ref "U3") (pin "3") (pinfunction "HB_3") (pintype "passive"))
    )
    (net (code "49") (name "Net-(U3-HI)") (class "Default")
      (node (ref "C26") (pin "1") (pinfunction "1_1") (pintype "passive"))
      (node (ref "R19") (pin "2") (pinfunction "2_2") (pintype "passive"))
      (node (ref "R20") (pin "2") (pinfunction "2_2") (pintype "passive"))
      (node (ref "U3") (pin "7") (pinfunction "HI_7") (pintype "passive"))
    )
    (net (code "50") (name "Net-(U3-LI)") (class "Default")
      (node (ref "C28") (pin "1") (pinfunction "1_1") (pintype "passive"))
      (node (ref "R21") (pin "2") (pinfunction "2_2") (pintype "passive"))
      (node (ref "R22") (pin "2") (pinfunction "2_2") (pintype "passive"))
      (node (ref "U3") (pin "8") (pinfunction "LI_8") (pintype "passive"))
    )
    (net (code "51") (name "Net-(U4-IN+)") (class "Default")
      (node (ref "C31") (pin "2") (pinfunction "2_2") (pintype "passive"))
      (node (ref "R27") (pin "2") (pinfunction "2_2") (pintype "passive"))
      (node (ref "U4") (pin "8") (pinfunction "IN+_8") (pintype "passive"))
    )
    (net (code "52") (name "Net-(U4-IN-)") (class "Default")
      (node (ref "C31") (pin "1") (pinfunction "1_1") (pintype "passive"))
      (node (ref "R31") (pin "2") (pinfunction "2_2") (pintype "passive"))
      (node (ref "U4") (pin "1") (pinfunction "IN-_1") (pintype "passive"))
    )
    (net (code "53") (name "Net-(U4-OUT)") (class "Default")
      (node (ref "R29") (pin "1") (pinfunction "1_1") (pintype "passive"))
      (node (ref "U4") (pin "5") (pinfunction "OUT_5") (pintype "passive"))
    )
    (net (code "54") (name "Net-(U5-IN+)") (class "Default")
      (node (ref "C32") (pin "2") (pinfunction "2_2") (pintype "passive"))
      (node (ref "R28") (pin "2") (pinfunction "2_2") (pintype "passive"))
      (node (ref "U5") (pin "8") (pinfunction "IN+_8") (pintype "passive"))
    )
    (net (code "55") (name "Net-(U5-IN-)") (class "Default")
      (node (ref "C32") (pin "1") (pinfunction "1_1") (pintype "passive"))
      (node (ref "R32") (pin "2") (pinfunction "2_2") (pintype "passive"))
      (node (ref "U5") (pin "1") (pinfunction "IN-_1") (pintype "passive"))
    )
    (net (code "56") (name "Net-(U5-OUT)") (class "Default")
      (node (ref "R30") (pin "1") (pinfunction "1_1") (pintype "passive"))
      (node (ref "U5") (pin "5") (pinfunction "OUT_5") (pintype "passive"))
    )
    (net (code "57") (name "Net-(U6-BST)") (class "Default")
      (node (ref "C41") (pin "2") (pinfunction "2_2") (pintype "passive"))
      (node (ref "U6") (pin "7") (pinfunction "BST_7") (pintype "bidirectional"))
    )
    (net (code "58") (name "Net-(U6-FB)") (class "Default")
      (node (ref "C50") (pin "1") (pinfunction "1_1") (pintype "passive"))
      (node (ref "R46") (pin "1") (pinfunction "1_1") (pintype "passive"))
      (node (ref "R49") (pin "1") (pinfunction "1_1") (pintype "passive"))
      (node (ref "U6") (pin "5") (pinfunction "FB_5") (pintype "bidirectional"))
    )
    (net (code "59") (name "Net-(U6-RON)") (class "Default")
      (node (ref "R36") (pin "2") (pinfunction "2_2") (pintype "passive"))
      (node (ref "U6") (pin "4") (pinfunction "RON_4") (pintype "bidirectional"))
    )
    (net (code "60") (name "Net-(U6-SW)") (class "Default")
      (node (ref "C41") (pin "1") (pinfunction "1_1") (pintype "passive"))
      (node (ref "L5") (pin "1") (pinfunction "1_1") (pintype "passive"))
      (node (ref "R44") (pin "1") (pinfunction "1_1") (pintype "passive"))
      (node (ref "U6") (pin "8") (pinfunction "SW_8") (pintype "bidirectional"))
    )
    (net (code "61") (name "Net-(U6-UVLO)") (class "Default")
      (node (ref "R35") (pin "2") (pinfunction "2_2") (pintype "passive"))
      (node (ref "R41") (pin "1") (pinfunction "1_1") (pintype "passive"))
      (node (ref "U6") (pin "3") (pinfunction "UVLO_3") (pintype "bidirectional"))
    )
    (net (code "62") (name "Net-(U6-VCC)") (class "Default")
      (node (ref "C39") (pin "2") (pinfunction "2_2") (pintype "passive"))
      (node (ref "U6") (pin "6") (pinfunction "VCC_6") (pintype "power_in"))
    )
    (net (code "63") (name "Net-(U7-BST)") (class "Default")
      (node (ref "C42") (pin "2") (pinfunction "2_2") (pintype "passive"))
      (node (ref "U7") (pin "7") (pinfunction "BST_7") (pintype "bidirectional"))
    )
    (net (code "64") (name "Net-(U7-FB)") (class "Default")
      (node (ref "C51") (pin "1") (pinfunction "1_1") (pintype "passive"))
      (node (ref "R47") (pin "1") (pinfunction "1_1") (pintype "passive"))
      (node (ref "R50") (pin "1") (pinfunction "1_1") (pintype "passive"))
      (node (ref "U7") (pin "5") (pinfunction "FB_5") (pintype "bidirectional"))
    )
    (net (code "65") (name "Net-(U7-RON)") (class "Default")
      (node (ref "R38") (pin "2") (pinfunction "2_2") (pintype "passive"))
      (node (ref "U7") (pin "4") (pinfunction "RON_4") (pintype "bidirectional"))
    )
    (net (code "66") (name "Net-(U7-SW)") (class "Default")
      (node (ref "C42") (pin "1") (pinfunction "1_1") (pintype "passive"))
      (node (ref "L6") (pin "1") (pinfunction "1_1") (pintype "passive"))
      (node (ref "R45") (pin "1") (pinfunction "1_1") (pintype "passive"))
      (node (ref "U7") (pin "8") (pinfunction "SW_8") (pintype "bidirectional"))
    )
    (net (code "67") (name "Net-(U7-UVLO)") (class "Default")
      (node (ref "R37") (pin "2") (pinfunction "2_2") (pintype "passive"))
      (node (ref "R42") (pin "1") (pinfunction "1_1") (pintype "passive"))
      (node (ref "U7") (pin "3") (pinfunction "UVLO_3") (pintype "bidirectional"))
    )
    (net (code "68") (name "Net-(U7-VCC)") (class "Default")
      (node (ref "C40") (pin "2") (pinfunction "2_2") (pintype "passive"))
      (node (ref "U7") (pin "6") (pinfunction "VCC_6") (pintype "power_in"))
    )
    (net (code "69") (name "Net-(U8-CII)") (class "Default")
      (node (ref "R43") (pin "1") (pinfunction "1_1") (pintype "passive"))
      (node (ref "R48") (pin "2") (pinfunction "2_2") (pintype "passive"))
      (node (ref "U8") (pin "5") (pinfunction "CII_5") (pintype "power_in"))
    )
    (net (code "70") (name "Net-(U8-DC)") (class "Default")
      (node (ref "R40") (pin "2") (pinfunction "2_2") (pintype "passive"))
      (node (ref "U8") (pin "8") (pinfunction "DC_8") (pintype "power_in"))
    )
    (net (code "71") (name "Net-(U8-Ipk)") (class "Default")
      (node (ref "L4") (pin "1") (pinfunction "1_1") (pintype "passive"))
      (node (ref "R39") (pin "2") (pinfunction "2_2") (pintype "passive"))
      (node (ref "R40") (pin "1") (pinfunction "1_1") (pintype "passive"))
      (node (ref "U8") (pin "7") (pinfunction "Ipk_7") (pintype "power_in"))
    )
    (net (code "72") (name "Net-(U8-SC)") (class "Default")
      (node (ref "D14") (pin "A") (pinfunction "A_A") (pintype "passive"))
      (node (ref "L4") (pin "2") (pinfunction "2_2") (pintype "passive"))
      (node (ref "U8") (pin "1") (pinfunction "SC_1") (pintype "power_in"))
    )
    (net (code "73") (name "Net-(U8-TC)") (class "Default")
      (node (ref "C52") (pin "2") (pinfunction "2_2") (pintype "passive"))
      (node (ref "U8") (pin "3") (pinfunction "TC_3") (pintype "power_in"))
    )
    (net (code "74") (name "Vpsu") (class "Default")
      (node (ref "C37") (pin "2") (pinfunction "2_2") (pintype "passive"))
      (node (ref "C38") (pin "2") (pinfunction "2_2") (pintype "passive"))
      (node (ref "C44") (pin "2") (pinfunction "2_2") (pintype "passive"))
      (node (ref "C45") (pin "1") (pinfunction "1_1") (pintype "passive"))
      (node (ref "D13") (pin "C") (pinfunction "C_C") (pintype "passive"))
      (node (ref "D14") (pin "C") (pinfunction "C_C") (pintype "passive"))
      (node (ref "R35") (pin "1") (pinfunction "1_1") (pintype "passive"))
      (node (ref "R36") (pin "1") (pinfunction "1_1") (pintype "passive"))
      (node (ref "R37") (pin "1") (pinfunction "1_1") (pintype "passive"))
      (node (ref "R38") (pin "1") (pinfunction "1_1") (pintype "passive"))
      (node (ref "R43") (pin "2") (pinfunction "2_2") (pintype "passive"))
      (node (ref "U6") (pin "2") (pinfunction "VIN_2") (pintype "input"))
      (node (ref "U7") (pin "2") (pinfunction "VIN_2") (pintype "input"))
    )
    (net (code "75") (name "unconnected-(U1-nPGD-Pad8)") (class "Default")
      (node (ref "U1") (pin "8") (pinfunction "nPGD_8") (pintype "passive"))
    )
    (net (code "76") (name "unconnected-(U2-nPGD-Pad8)") (class "Default")
      (node (ref "U2") (pin "8") (pinfunction "nPGD_8") (pintype "passive"))
    )
  )
)
